# Replicape_B0.net
KiCad netlist of a schematic drawn in EAGLE
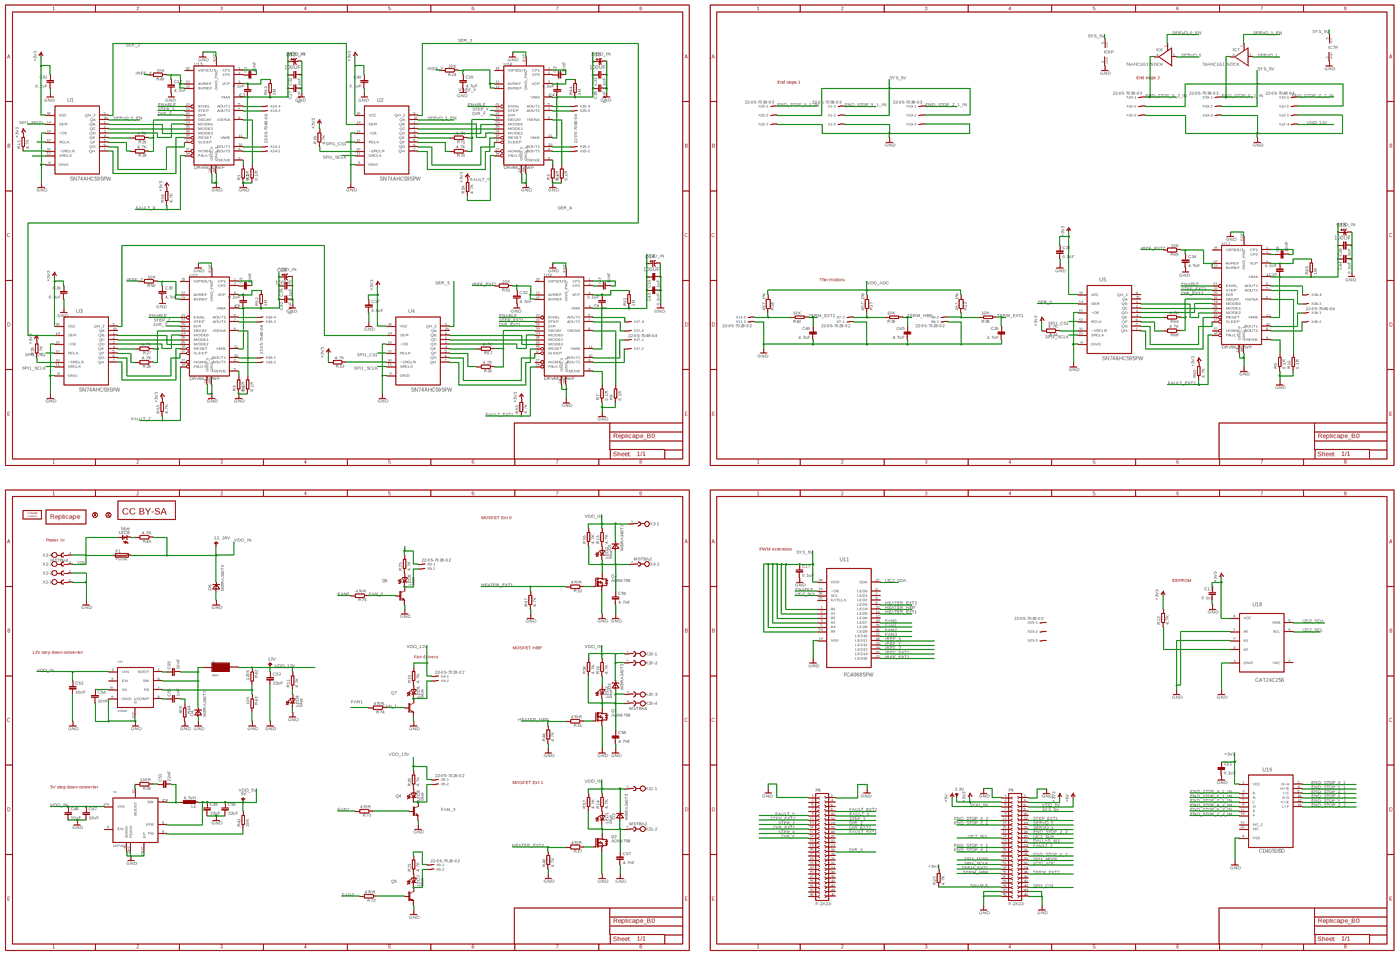
[diagram p0: schematic, sheet 1, overview]
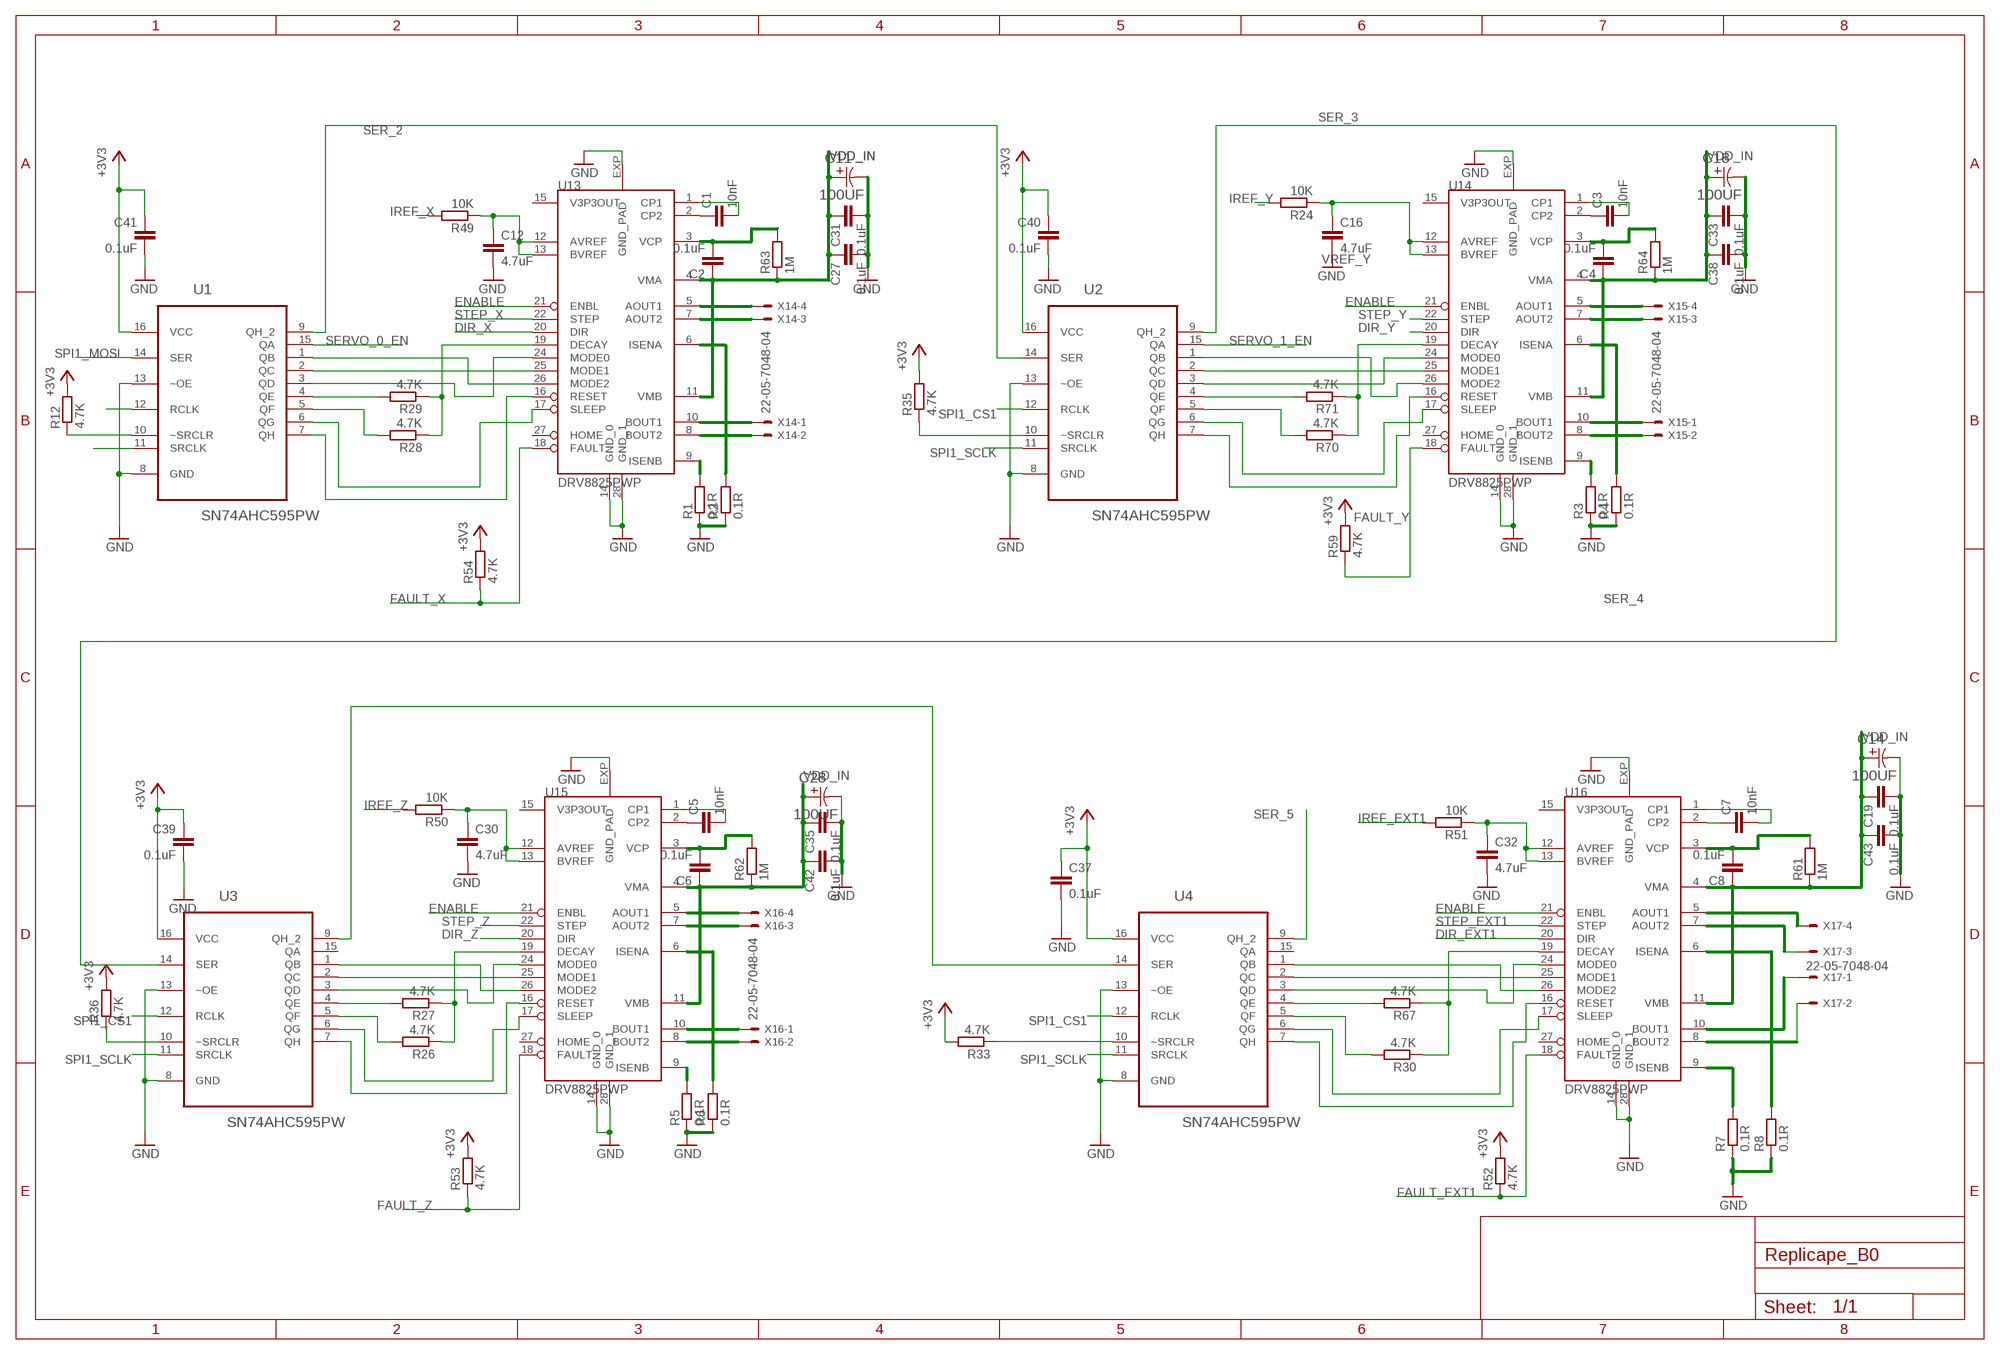
[diagram p1: schematic, sheet 1, part 1 of 4]
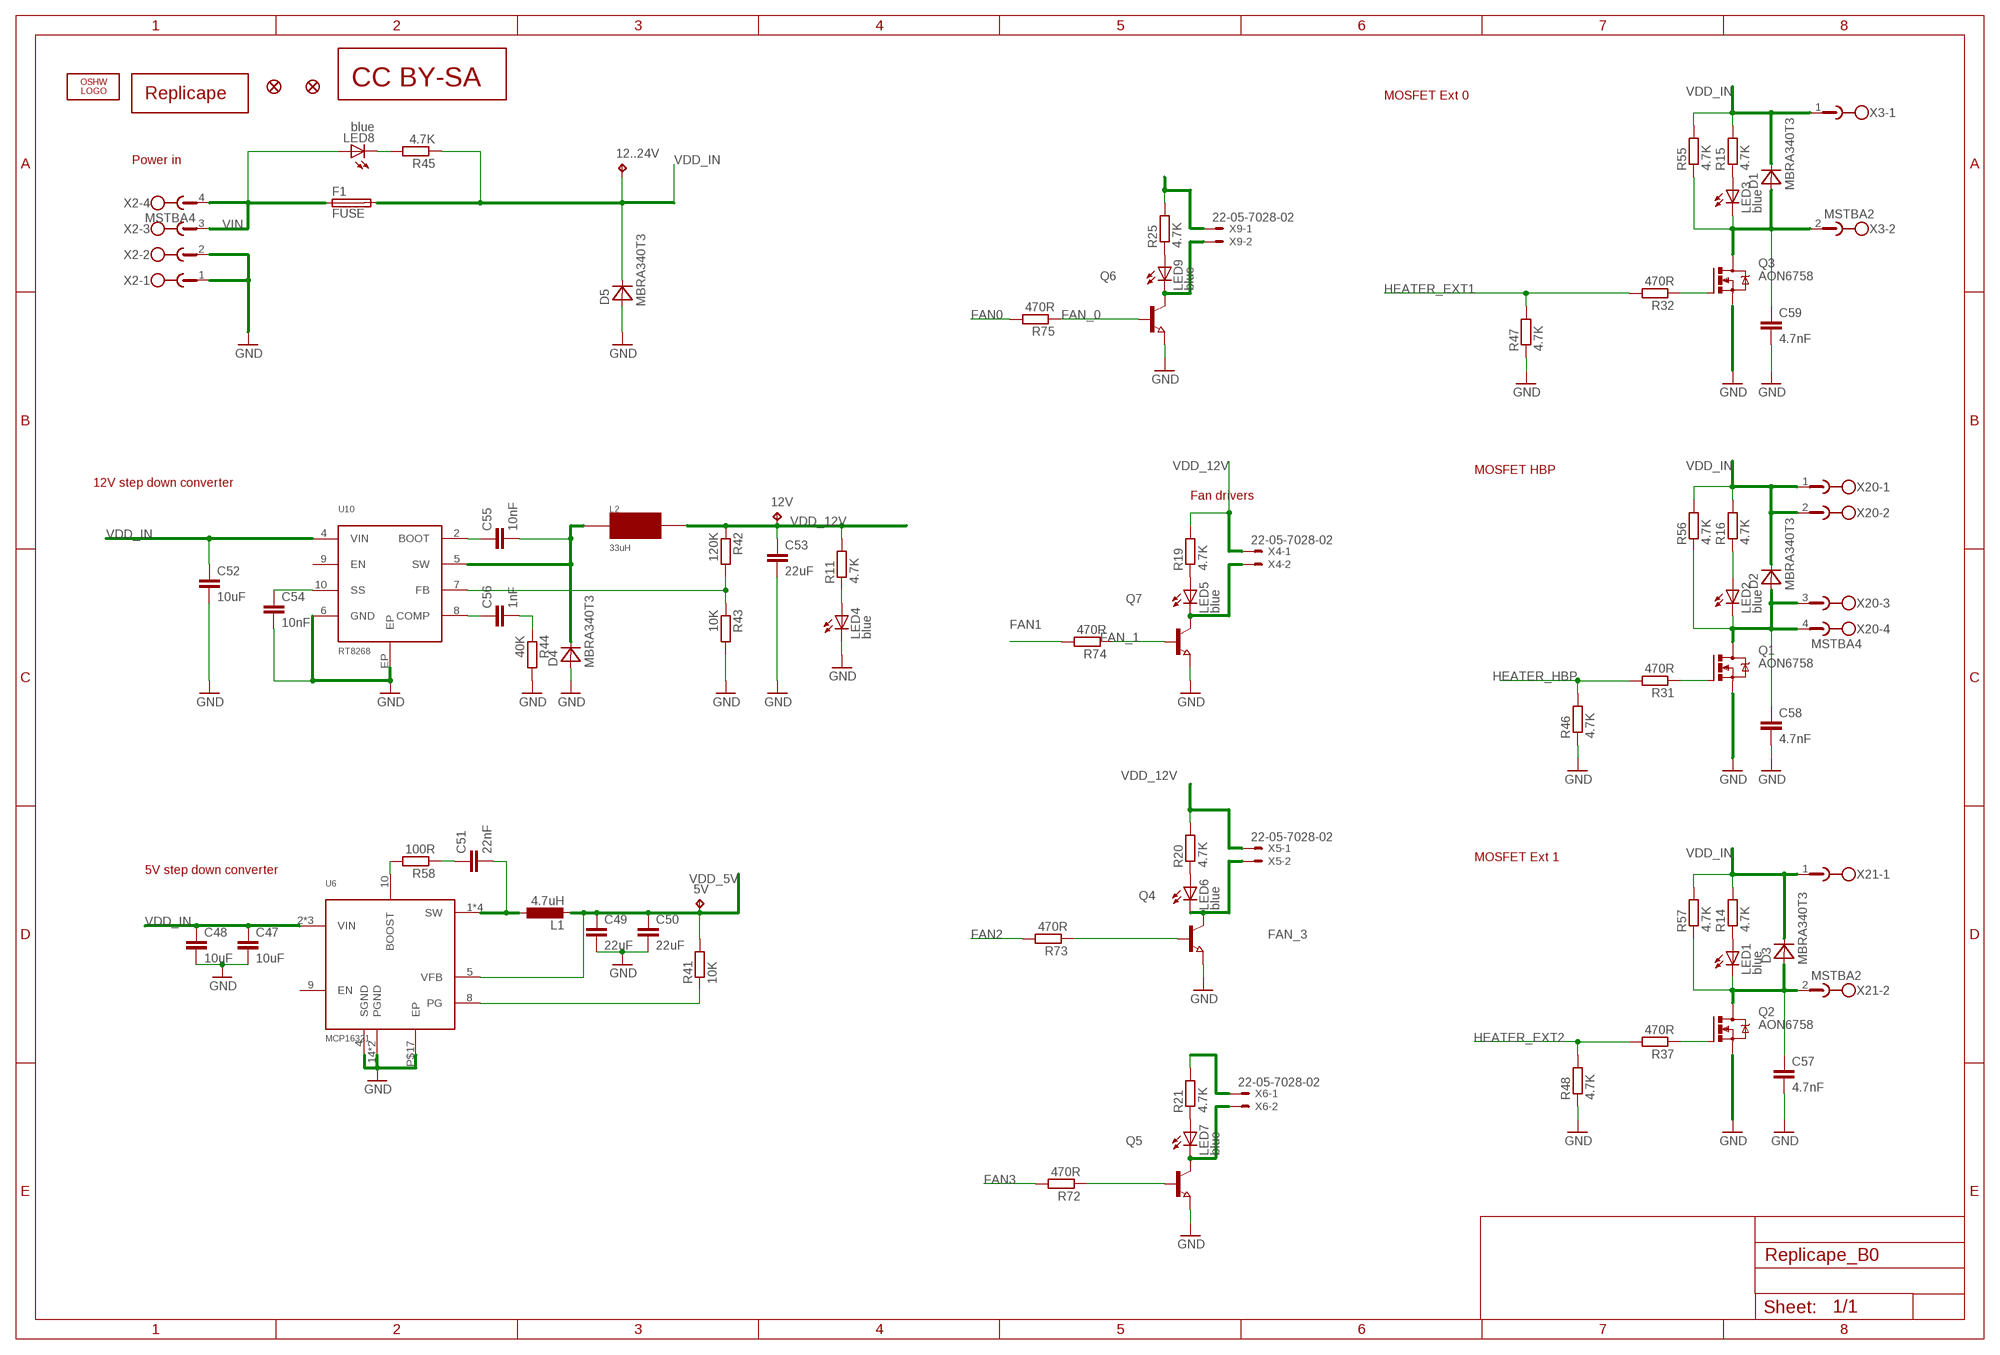
[diagram p2: schematic, sheet 1, part 2 of 4]
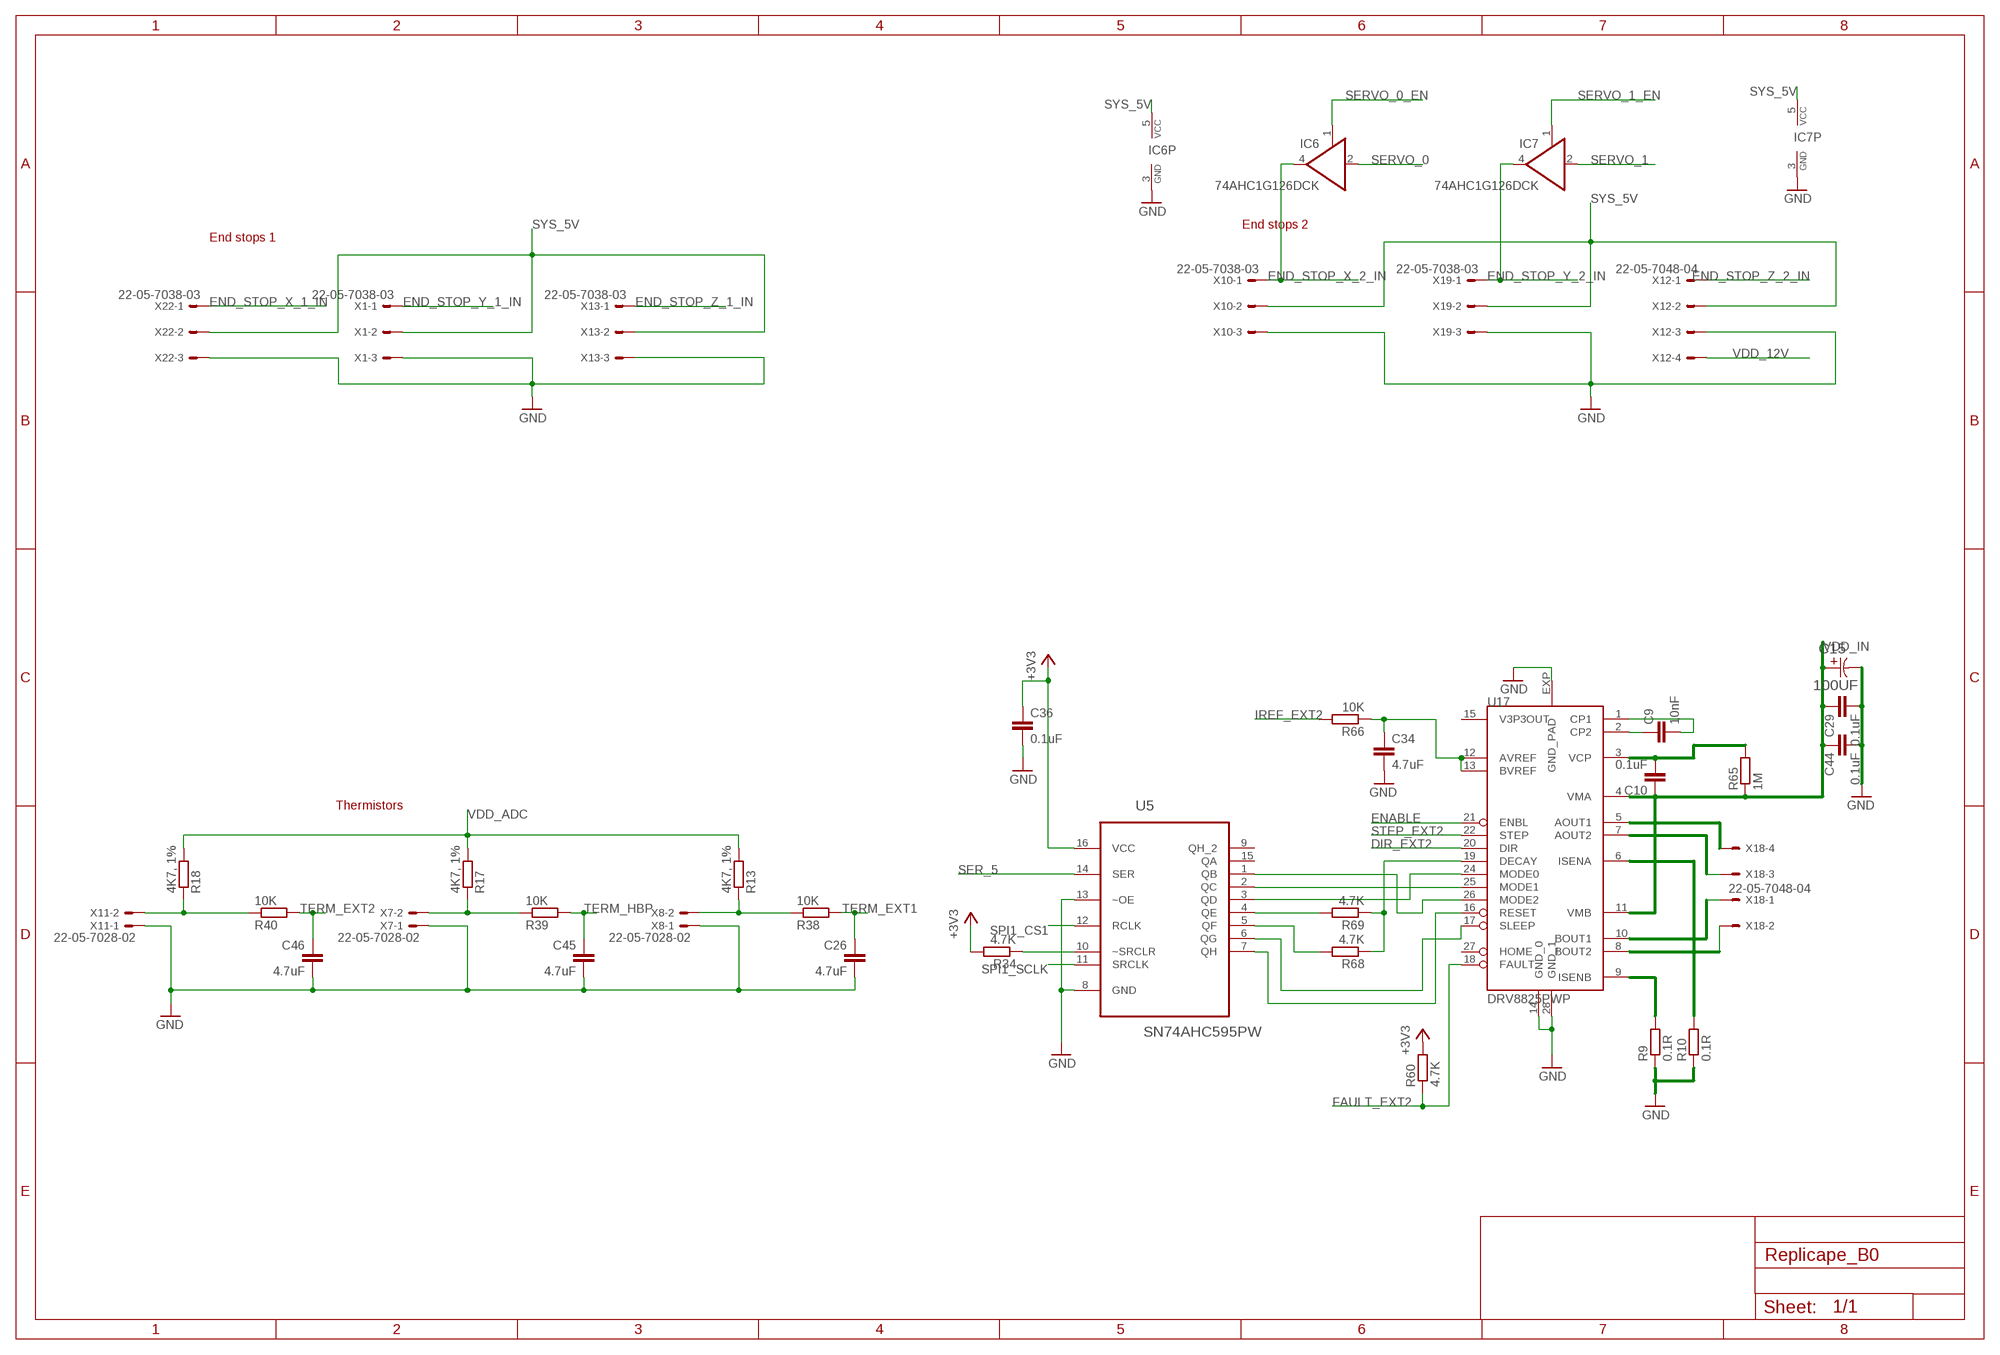
[diagram p3: schematic, sheet 1, part 3 of 4]
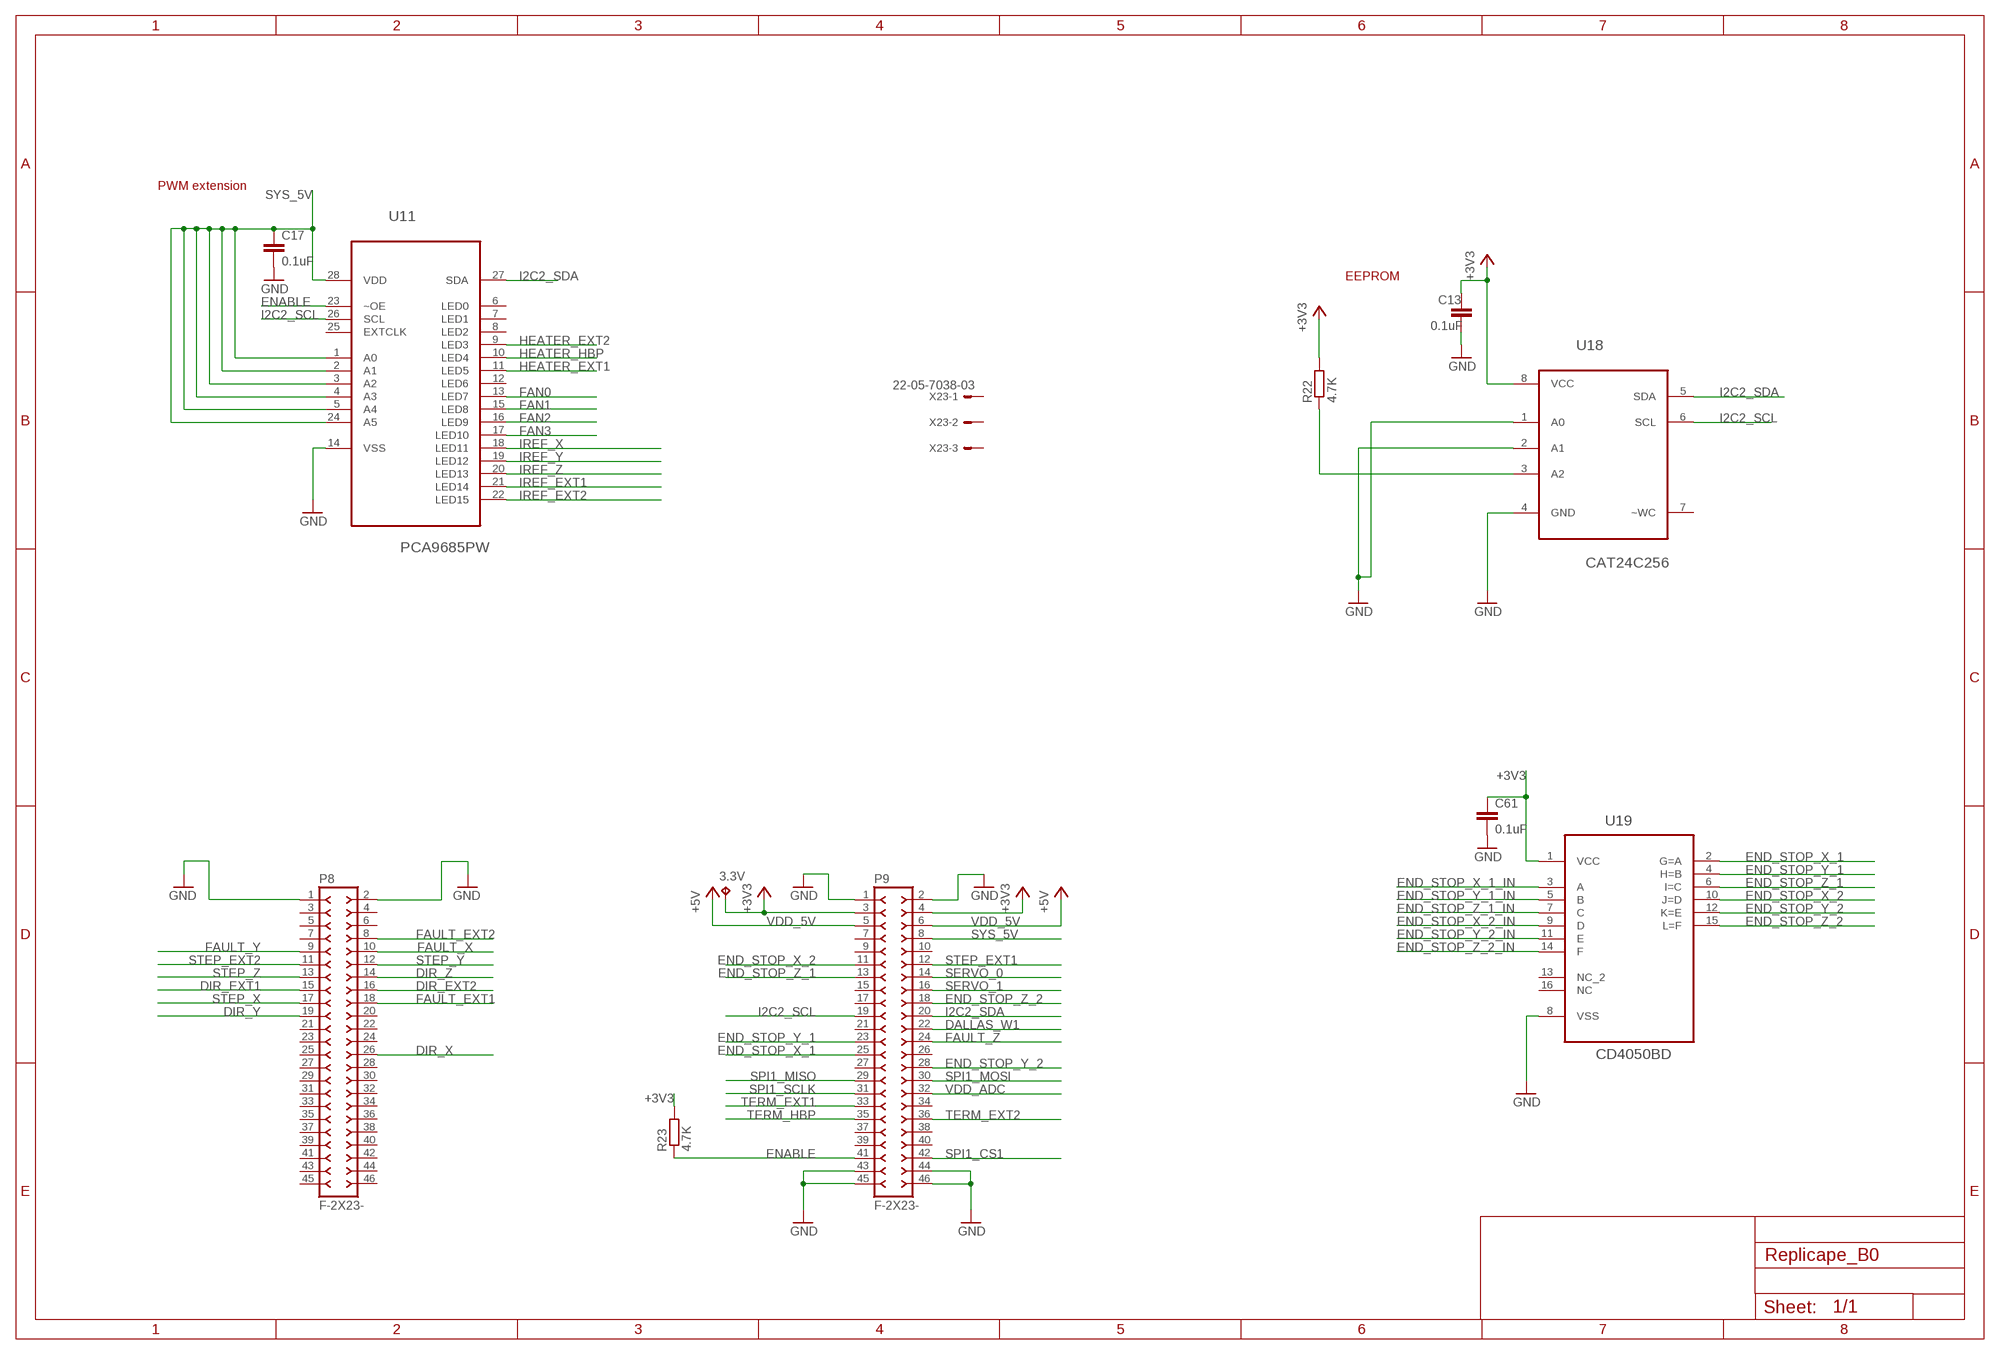
[diagram p4: schematic, sheet 1, part 4 of 4]

(export (version "E")
  (design (tool "Eeschema 10.0.6"))
  (components
    (comp (ref "3.3V")
      (value "TPB1,27")
      (footprint "eagle-import:B1,27")
      (libsource (lib "eagle-import") (part "TPB1,27"))
    )
    (comp (ref "5V")
      (value "TPB1,27")
      (footprint "eagle-import:B1,27")
      (libsource (lib "eagle-import") (part "TPB1,27"))
    )
    (comp (ref "12..24V")
      (value "TPB1,27")
      (footprint "eagle-import:B1,27")
      (libsource (lib "eagle-import") (part "TPB1,27"))
    )
    (comp (ref "12V")
      (value "TPB1,27")
      (footprint "eagle-import:B1,27")
      (libsource (lib "eagle-import") (part "TPB1,27"))
    )
    (comp (ref "C1")
      (value "10nF")
      (footprint "eagle-import:C0402")
      (libsource (lib "eagle-import") (part "C-EUC0402"))
    )
    (comp (ref "C2")
      (value "0.1uF")
      (footprint "eagle-import:C0402")
      (libsource (lib "eagle-import") (part "C-EUC0402"))
    )
    (comp (ref "C3")
      (value "10nF")
      (footprint "eagle-import:C0402")
      (libsource (lib "eagle-import") (part "C-EUC0402"))
    )
    (comp (ref "C4")
      (value "0.1uF")
      (footprint "eagle-import:C0402")
      (libsource (lib "eagle-import") (part "C-EUC0402"))
    )
    (comp (ref "C5")
      (value "10nF")
      (footprint "eagle-import:C0402")
      (libsource (lib "eagle-import") (part "C-EUC0402"))
    )
    (comp (ref "C6")
      (value "0.1uF")
      (footprint "eagle-import:C0402")
      (libsource (lib "eagle-import") (part "C-EUC0402"))
    )
    (comp (ref "C7")
      (value "10nF")
      (footprint "eagle-import:C0402")
      (libsource (lib "eagle-import") (part "C-EUC0402"))
    )
    (comp (ref "C8")
      (value "0.1uF")
      (footprint "eagle-import:C0402")
      (libsource (lib "eagle-import") (part "C-EUC0402"))
    )
    (comp (ref "C9")
      (value "10nF")
      (footprint "eagle-import:C0402")
      (libsource (lib "eagle-import") (part "C-EUC0402"))
    )
    (comp (ref "C10")
      (value "0.1uF")
      (footprint "eagle-import:C0402")
      (libsource (lib "eagle-import") (part "C-EUC0402"))
    )
    (comp (ref "C11")
      (value "100UF")
      (footprint "eagle-import:CAPAE660X800N")
      (fields (field (name "MPN") "EEE-FK1V101XP") (field (name "TOLERANCE") "±20 %"))
      (libsource (lib "eagle-import") (part "EEE--CASE-D8FK1V101XP"))
    )
    (comp (ref "C12")
      (value "4.7uF")
      (footprint "eagle-import:C0402")
      (libsource (lib "eagle-import") (part "C-EUC0402"))
    )
    (comp (ref "C13")
      (value "0.1uF")
      (footprint "eagle-import:C0402")
      (libsource (lib "eagle-import") (part "C-EUC0402"))
    )
    (comp (ref "C14")
      (value "100UF")
      (footprint "eagle-import:CAPAE660X800N")
      (fields (field (name "MPN") "EEE-FK1V101XP") (field (name "TOLERANCE") "±20 %"))
      (libsource (lib "eagle-import") (part "EEE--CASE-D8FK1V101XP"))
    )
    (comp (ref "C15")
      (value "100UF")
      (footprint "eagle-import:CAPAE660X800N")
      (fields (field (name "MPN") "EEE-FK1V101XP") (field (name "TOLERANCE") "±20 %"))
      (libsource (lib "eagle-import") (part "EEE--CASE-D8FK1V101XP"))
    )
    (comp (ref "C16")
      (value "4.7uF")
      (footprint "eagle-import:C0402")
      (libsource (lib "eagle-import") (part "C-EUC0402"))
    )
    (comp (ref "C17")
      (value "0.1uF")
      (footprint "eagle-import:C0402")
      (libsource (lib "eagle-import") (part "C-EUC0402"))
    )
    (comp (ref "C18")
      (value "100UF")
      (footprint "eagle-import:CAPAE660X800N")
      (fields (field (name "MPN") "EEE-FK1V101XP") (field (name "TOLERANCE") "±20 %"))
      (libsource (lib "eagle-import") (part "EEE--CASE-D8FK1V101XP"))
    )
    (comp (ref "C19")
      (value "0.1uF")
      (footprint "eagle-import:C0402")
      (libsource (lib "eagle-import") (part "C-EUC0402"))
    )
    (comp (ref "C26")
      (value "4.7uF")
      (footprint "eagle-import:C0402")
      (libsource (lib "eagle-import") (part "C-EUC0402"))
    )
    (comp (ref "C27")
      (value "0.1uF")
      (footprint "eagle-import:C0402")
      (libsource (lib "eagle-import") (part "C-EUC0402"))
    )
    (comp (ref "C28")
      (value "100UF")
      (footprint "eagle-import:CAPAE660X800N")
      (fields (field (name "MPN") "EEE-FK1V101XP") (field (name "TOLERANCE") "±20 %"))
      (libsource (lib "eagle-import") (part "EEE--CASE-D8FK1V101XP"))
    )
    (comp (ref "C29")
      (value "0.1uF")
      (footprint "eagle-import:C0402")
      (libsource (lib "eagle-import") (part "C-EUC0402"))
    )
    (comp (ref "C30")
      (value "4.7uF")
      (footprint "eagle-import:C0402")
      (libsource (lib "eagle-import") (part "C-EUC0402"))
    )
    (comp (ref "C31")
      (value "0.1uF")
      (footprint "eagle-import:C0402")
      (libsource (lib "eagle-import") (part "C-EUC0402"))
    )
    (comp (ref "C32")
      (value "4.7uF")
      (footprint "eagle-import:C0402")
      (libsource (lib "eagle-import") (part "C-EUC0402"))
    )
    (comp (ref "C33")
      (value "0.1uF")
      (footprint "eagle-import:C0402")
      (libsource (lib "eagle-import") (part "C-EUC0402"))
    )
    (comp (ref "C34")
      (value "4.7uF")
      (footprint "eagle-import:C0402")
      (libsource (lib "eagle-import") (part "C-EUC0402"))
    )
    (comp (ref "C35")
      (value "0.1uF")
      (footprint "eagle-import:C0402")
      (libsource (lib "eagle-import") (part "C-EUC0402"))
    )
    (comp (ref "C36")
      (value "0.1uF")
      (footprint "eagle-import:C0402")
      (libsource (lib "eagle-import") (part "C-EUC0402"))
    )
    (comp (ref "C37")
      (value "0.1uF")
      (footprint "eagle-import:C0402")
      (libsource (lib "eagle-import") (part "C-EUC0402"))
    )
    (comp (ref "C38")
      (value "0.1uF")
      (footprint "eagle-import:C0402")
      (libsource (lib "eagle-import") (part "C-EUC0402"))
    )
    (comp (ref "C39")
      (value "0.1uF")
      (footprint "eagle-import:C0402")
      (libsource (lib "eagle-import") (part "C-EUC0402"))
    )
    (comp (ref "C40")
      (value "0.1uF")
      (footprint "eagle-import:C0402")
      (libsource (lib "eagle-import") (part "C-EUC0402"))
    )
    (comp (ref "C41")
      (value "0.1uF")
      (footprint "eagle-import:C0402")
      (libsource (lib "eagle-import") (part "C-EUC0402"))
    )
    (comp (ref "C42")
      (value "0.1uF")
      (footprint "eagle-import:C0402")
      (libsource (lib "eagle-import") (part "C-EUC0402"))
    )
    (comp (ref "C43")
      (value "0.1uF")
      (footprint "eagle-import:C0402")
      (libsource (lib "eagle-import") (part "C-EUC0402"))
    )
    (comp (ref "C44")
      (value "0.1uF")
      (footprint "eagle-import:C0402")
      (libsource (lib "eagle-import") (part "C-EUC0402"))
    )
    (comp (ref "C45")
      (value "4.7uF")
      (footprint "eagle-import:C0402")
      (libsource (lib "eagle-import") (part "C-EUC0402"))
    )
    (comp (ref "C46")
      (value "4.7uF")
      (footprint "eagle-import:C0402")
      (libsource (lib "eagle-import") (part "C-EUC0402"))
    )
    (comp (ref "C47")
      (value "10uF")
      (footprint "eagle-import:C1206")
      (libsource (lib "eagle-import") (part "C-EUC1206"))
    )
    (comp (ref "C48")
      (value "10uF")
      (footprint "eagle-import:C1206")
      (libsource (lib "eagle-import") (part "C-EUC1206"))
    )
    (comp (ref "C49")
      (value "22uF")
      (footprint "eagle-import:C0805")
      (libsource (lib "eagle-import") (part "C-EUC0805"))
    )
    (comp (ref "C50")
      (value "22uF")
      (footprint "eagle-import:C0805")
      (libsource (lib "eagle-import") (part "C-EUC0805"))
    )
    (comp (ref "C51")
      (value "22nF")
      (footprint "eagle-import:C0402")
      (libsource (lib "eagle-import") (part "C-EUC0402"))
    )
    (comp (ref "C52")
      (value "10uF")
      (footprint "eagle-import:C1206")
      (libsource (lib "eagle-import") (part "C-EUC1206"))
    )
    (comp (ref "C53")
      (value "22uF")
      (footprint "eagle-import:C0805")
      (libsource (lib "eagle-import") (part "C-EUC0805"))
    )
    (comp (ref "C54")
      (value "10nF")
      (footprint "eagle-import:C0402")
      (libsource (lib "eagle-import") (part "C-EUC0402"))
    )
    (comp (ref "C55")
      (value "10nF")
      (footprint "eagle-import:C0402")
      (libsource (lib "eagle-import") (part "C-EUC0402"))
    )
    (comp (ref "C56")
      (value "1nF")
      (footprint "eagle-import:C0402")
      (libsource (lib "eagle-import") (part "C-EUC0402"))
    )
    (comp (ref "C57")
      (value "4.7nF")
      (footprint "eagle-import:C0402")
      (libsource (lib "eagle-import") (part "C-EUC0402"))
    )
    (comp (ref "C58")
      (value "4.7nF")
      (footprint "eagle-import:C0402")
      (libsource (lib "eagle-import") (part "C-EUC0402"))
    )
    (comp (ref "C59")
      (value "4.7nF")
      (footprint "eagle-import:C0402")
      (libsource (lib "eagle-import") (part "C-EUC0402"))
    )
    (comp (ref "C61")
      (value "0.1uF")
      (footprint "eagle-import:C0402")
      (libsource (lib "eagle-import") (part "C-EUC0402"))
    )
    (comp (ref "D1")
      (value "MBRA340T3")
      (footprint "eagle-import:SMA")
      (libsource (lib "eagle-import") (part "MBRA340T3"))
    )
    (comp (ref "D2")
      (value "MBRA340T3")
      (footprint "eagle-import:SMA")
      (libsource (lib "eagle-import") (part "MBRA340T3"))
    )
    (comp (ref "D3")
      (value "MBRA340T3")
      (footprint "eagle-import:SMA")
      (libsource (lib "eagle-import") (part "MBRA340T3"))
    )
    (comp (ref "D4")
      (value "MBRA340T3")
      (footprint "eagle-import:SMA")
      (libsource (lib "eagle-import") (part "MBRA340T3"))
    )
    (comp (ref "D5")
      (value "MBRA340T3")
      (footprint "eagle-import:SMA")
      (libsource (lib "eagle-import") (part "MBRA340T3"))
    )
    (comp (ref "F1")
      (value "FUSE")
      (footprint "eagle-import:3557")
      (libsource (lib "eagle-import") (part "FUSE"))
    )
    (comp (ref "IC6")
      (value "74AHC1G126DCK")
      (footprint "eagle-import:SC70-5")
      (libsource (lib "eagle-import") (part "741G126DCKAHC"))
    )
    (comp (ref "IC7")
      (value "74AHC1G126DCK")
      (footprint "eagle-import:SC70-5")
      (libsource (lib "eagle-import") (part "741G126DCKAHC"))
    )
    (comp (ref "JP1")
      (value "FIDUCIAL1X2.5")
      (footprint "eagle-import:FIDUCIAL-1X2.5")
      (libsource (lib "eagle-import") (part "FIDUCIAL1X2.5"))
    )
    (comp (ref "JP2")
      (value "FIDUCIAL1X2.5")
      (footprint "eagle-import:FIDUCIAL-1X2.5")
      (libsource (lib "eagle-import") (part "FIDUCIAL1X2.5"))
    )
    (comp (ref "L1")
      (value "4.7uH")
      (footprint "eagle-import:VLC5020")
      (libsource (lib "eagle-import") (part "L-EU"))
    )
    (comp (ref "L2")
      (value "33uH")
      (footprint "eagle-import:NR8040T330")
      (libsource (lib "eagle-import") (part "RT8040T330"))
    )
    (comp (ref "LED1")
      (value "blue")
      (footprint "eagle-import:CHIP-LED0603")
      (libsource (lib "eagle-import") (part "LEDCHIP-LED0603"))
    )
    (comp (ref "LED2")
      (value "blue")
      (footprint "eagle-import:CHIP-LED0603")
      (libsource (lib "eagle-import") (part "LEDCHIP-LED0603"))
    )
    (comp (ref "LED3")
      (value "blue")
      (footprint "eagle-import:CHIP-LED0603")
      (libsource (lib "eagle-import") (part "LEDCHIP-LED0603"))
    )
    (comp (ref "LED4")
      (value "blue")
      (footprint "eagle-import:CHIP-LED0603")
      (libsource (lib "eagle-import") (part "LEDCHIP-LED0603"))
    )
    (comp (ref "LED5")
      (value "blue")
      (footprint "eagle-import:CHIP-LED0603")
      (libsource (lib "eagle-import") (part "LEDCHIP-LED0603"))
    )
    (comp (ref "LED6")
      (value "blue")
      (footprint "eagle-import:CHIP-LED0603")
      (libsource (lib "eagle-import") (part "LEDCHIP-LED0603"))
    )
    (comp (ref "LED7")
      (value "blue")
      (footprint "eagle-import:CHIP-LED0603")
      (libsource (lib "eagle-import") (part "LEDCHIP-LED0603"))
    )
    (comp (ref "LED8")
      (value "blue")
      (footprint "eagle-import:CHIP-LED0603")
      (libsource (lib "eagle-import") (part "LEDCHIP-LED0603"))
    )
    (comp (ref "LED9")
      (value "blue")
      (footprint "eagle-import:CHIP-LED0603")
      (libsource (lib "eagle-import") (part "LEDCHIP-LED0603"))
    )
    (comp (ref "LOGO1")
      (value "OSHW_LOGO_FILLX0200-NT")
      (footprint "eagle-import:OSHW_FILLX200_NOTEXT")
      (libsource (lib "eagle-import") (part "OSHW_LOGO_FILLX0200-NT"))
    )
    (comp (ref "P8")
      (value "F-2X23-")
      (footprint "eagle-import:DIL-100-2X23")
      (libsource (lib "eagle-import") (part "F-2X23-"))
    )
    (comp (ref "P9")
      (value "F-2X23-")
      (footprint "eagle-import:DIL-100-2X23")
      (libsource (lib "eagle-import") (part "F-2X23-"))
    )
    (comp (ref "Q1")
      (value "AON6758")
      (footprint "eagle-import:8-DFN-EP-(5X6)")
      (libsource (lib "eagle-import") (part "AON6758"))
    )
    (comp (ref "Q2")
      (value "AON6758")
      (footprint "eagle-import:8-DFN-EP-(5X6)")
      (libsource (lib "eagle-import") (part "AON6758"))
    )
    (comp (ref "Q3")
      (value "AON6758")
      (footprint "eagle-import:8-DFN-EP-(5X6)")
      (libsource (lib "eagle-import") (part "AON6758"))
    )
    (comp (ref "Q4")
      (value "NPN-TRANSISTOR_SOT23")
      (footprint "eagle-import:SOT23")
      (libsource (lib "eagle-import") (part "NPN-TRANSISTOR_SOT23"))
    )
    (comp (ref "Q5")
      (value "NPN-TRANSISTOR_SOT23")
      (footprint "eagle-import:SOT23")
      (libsource (lib "eagle-import") (part "NPN-TRANSISTOR_SOT23"))
    )
    (comp (ref "Q6")
      (value "NPN-TRANSISTOR_SOT23")
      (footprint "eagle-import:SOT23")
      (libsource (lib "eagle-import") (part "NPN-TRANSISTOR_SOT23"))
    )
    (comp (ref "Q7")
      (value "NPN-TRANSISTOR_SOT23")
      (footprint "eagle-import:SOT23")
      (libsource (lib "eagle-import") (part "NPN-TRANSISTOR_SOT23"))
    )
    (comp (ref "R1")
      (value "0.1R")
      (footprint "eagle-import:R0805")
      (libsource (lib "eagle-import") (part "R-EU_R0805"))
    )
    (comp (ref "R2")
      (value "0.1R")
      (footprint "eagle-import:R0805")
      (libsource (lib "eagle-import") (part "R-EU_R0805"))
    )
    (comp (ref "R3")
      (value "0.1R")
      (footprint "eagle-import:R0805")
      (libsource (lib "eagle-import") (part "R-EU_R0805"))
    )
    (comp (ref "R4")
      (value "0.1R")
      (footprint "eagle-import:R0805")
      (libsource (lib "eagle-import") (part "R-EU_R0805"))
    )
    (comp (ref "R5")
      (value "0.1R")
      (footprint "eagle-import:R0805")
      (libsource (lib "eagle-import") (part "R-EU_R0805"))
    )
    (comp (ref "R6")
      (value "0.1R")
      (footprint "eagle-import:R0805")
      (libsource (lib "eagle-import") (part "R-EU_R0805"))
    )
    (comp (ref "R7")
      (value "0.1R")
      (footprint "eagle-import:R0805")
      (libsource (lib "eagle-import") (part "R-EU_R0805"))
    )
    (comp (ref "R8")
      (value "0.1R")
      (footprint "eagle-import:R0805")
      (libsource (lib "eagle-import") (part "R-EU_R0805"))
    )
    (comp (ref "R9")
      (value "0.1R")
      (footprint "eagle-import:R0805")
      (libsource (lib "eagle-import") (part "R-EU_R0805"))
    )
    (comp (ref "R10")
      (value "0.1R")
      (footprint "eagle-import:R0805")
      (libsource (lib "eagle-import") (part "R-EU_R0805"))
    )
    (comp (ref "R11")
      (value "4.7K")
      (footprint "eagle-import:R0402")
      (libsource (lib "eagle-import") (part "R-EU_R0402"))
    )
    (comp (ref "R12")
      (value "4.7K")
      (footprint "eagle-import:R0402")
      (libsource (lib "eagle-import") (part "R-EU_R0402"))
    )
    (comp (ref "R13")
      (value "4K7, 1%")
      (footprint "eagle-import:R0402")
      (libsource (lib "eagle-import") (part "R-EU_R0402"))
    )
    (comp (ref "R14")
      (value "4.7K")
      (footprint "eagle-import:R0402")
      (libsource (lib "eagle-import") (part "R-EU_R0402"))
    )
    (comp (ref "R15")
      (value "4.7K")
      (footprint "eagle-import:R0402")
      (libsource (lib "eagle-import") (part "R-EU_R0402"))
    )
    (comp (ref "R16")
      (value "4.7K")
      (footprint "eagle-import:R0402")
      (libsource (lib "eagle-import") (part "R-EU_R0402"))
    )
    (comp (ref "R17")
      (value "4K7, 1%")
      (footprint "eagle-import:R0402")
      (libsource (lib "eagle-import") (part "R-EU_R0402"))
    )
    (comp (ref "R18")
      (value "4K7, 1%")
      (footprint "eagle-import:R0402")
      (libsource (lib "eagle-import") (part "R-EU_R0402"))
    )
    (comp (ref "R19")
      (value "4.7K")
      (footprint "eagle-import:R0402")
      (libsource (lib "eagle-import") (part "R-EU_R0402"))
    )
    (comp (ref "R20")
      (value "4.7K")
      (footprint "eagle-import:R0402")
      (libsource (lib "eagle-import") (part "R-EU_R0402"))
    )
    (comp (ref "R21")
      (value "4.7K")
      (footprint "eagle-import:R0402")
      (libsource (lib "eagle-import") (part "R-EU_R0402"))
    )
    (comp (ref "R22")
      (value "4.7K")
      (footprint "eagle-import:R0402")
      (libsource (lib "eagle-import") (part "R-EU_R0402"))
    )
    (comp (ref "R23")
      (value "4.7K")
      (footprint "eagle-import:R0402")
      (libsource (lib "eagle-import") (part "R-EU_R0402"))
    )
    (comp (ref "R24")
      (value "10K")
      (footprint "eagle-import:R0402")
      (libsource (lib "eagle-import") (part "R-EU_R0402"))
    )
    (comp (ref "R25")
      (value "4.7K")
      (footprint "eagle-import:R0402")
      (libsource (lib "eagle-import") (part "R-EU_R0402"))
    )
    (comp (ref "R26")
      (value "4.7K")
      (footprint "eagle-import:R0402")
      (libsource (lib "eagle-import") (part "R-EU_R0402"))
    )
    (comp (ref "R27")
      (value "4.7K")
      (footprint "eagle-import:R0402")
      (libsource (lib "eagle-import") (part "R-EU_R0402"))
    )
    (comp (ref "R28")
      (value "4.7K")
      (footprint "eagle-import:R0402")
      (libsource (lib "eagle-import") (part "R-EU_R0402"))
    )
    (comp (ref "R29")
      (value "4.7K")
      (footprint "eagle-import:R0402")
      (libsource (lib "eagle-import") (part "R-EU_R0402"))
    )
    (comp (ref "R30")
      (value "4.7K")
      (footprint "eagle-import:R0402")
      (libsource (lib "eagle-import") (part "R-EU_R0402"))
    )
    (comp (ref "R31")
      (value "470R")
      (footprint "eagle-import:R0402")
      (libsource (lib "eagle-import") (part "R-EU_R0402"))
    )
    (comp (ref "R32")
      (value "470R")
      (footprint "eagle-import:R0402")
      (libsource (lib "eagle-import") (part "R-EU_R0402"))
    )
    (comp (ref "R33")
      (value "4.7K")
      (footprint "eagle-import:R0402")
      (libsource (lib "eagle-import") (part "R-EU_R0402"))
    )
    (comp (ref "R34")
      (value "4.7K")
      (footprint "eagle-import:R0402")
      (libsource (lib "eagle-import") (part "R-EU_R0402"))
    )
    (comp (ref "R35")
      (value "4.7K")
      (footprint "eagle-import:R0402")
      (libsource (lib "eagle-import") (part "R-EU_R0402"))
    )
    (comp (ref "R36")
      (value "4.7K")
      (footprint "eagle-import:R0402")
      (libsource (lib "eagle-import") (part "R-EU_R0402"))
    )
    (comp (ref "R37")
      (value "470R")
      (footprint "eagle-import:R0402")
      (libsource (lib "eagle-import") (part "R-EU_R0402"))
    )
    (comp (ref "R38")
      (value "10K")
      (footprint "eagle-import:R0402")
      (libsource (lib "eagle-import") (part "R-EU_R0402"))
    )
    (comp (ref "R39")
      (value "10K")
      (footprint "eagle-import:R0402")
      (libsource (lib "eagle-import") (part "R-EU_R0402"))
    )
    (comp (ref "R40")
      (value "10K")
      (footprint "eagle-import:R0402")
      (libsource (lib "eagle-import") (part "R-EU_R0402"))
    )
    (comp (ref "R41")
      (value "10K")
      (footprint "eagle-import:R0402")
      (libsource (lib "eagle-import") (part "R-EU_R0402"))
    )
    (comp (ref "R42")
      (value "120K")
      (footprint "eagle-import:R0402")
      (libsource (lib "eagle-import") (part "R-EU_R0402"))
    )
    (comp (ref "R43")
      (value "10K")
      (footprint "eagle-import:R0402")
      (libsource (lib "eagle-import") (part "R-EU_R0402"))
    )
    (comp (ref "R44")
      (value "40K")
      (footprint "eagle-import:R0402")
      (libsource (lib "eagle-import") (part "R-EU_R0402"))
    )
    (comp (ref "R45")
      (value "4.7K")
      (footprint "eagle-import:R0402")
      (libsource (lib "eagle-import") (part "R-EU_R0402"))
    )
    (comp (ref "R46")
      (value "4.7K")
      (footprint "eagle-import:R0402")
      (libsource (lib "eagle-import") (part "R-EU_R0402"))
    )
    (comp (ref "R47")
      (value "4.7K")
      (footprint "eagle-import:R0402")
      (libsource (lib "eagle-import") (part "R-EU_R0402"))
    )
    (comp (ref "R48")
      (value "4.7K")
      (footprint "eagle-import:R0402")
      (libsource (lib "eagle-import") (part "R-EU_R0402"))
    )
    (comp (ref "R49")
      (value "10K")
      (footprint "eagle-import:R0402")
      (libsource (lib "eagle-import") (part "R-EU_R0402"))
    )
    (comp (ref "R50")
      (value "10K")
      (footprint "eagle-import:R0402")
      (libsource (lib "eagle-import") (part "R-EU_R0402"))
    )
    (comp (ref "R51")
      (value "10K")
      (footprint "eagle-import:R0402")
      (libsource (lib "eagle-import") (part "R-EU_R0402"))
    )
    (comp (ref "R52")
      (value "4.7K")
      (footprint "eagle-import:R0402")
      (libsource (lib "eagle-import") (part "R-EU_R0402"))
    )
    (comp (ref "R53")
      (value "4.7K")
      (footprint "eagle-import:R0402")
      (libsource (lib "eagle-import") (part "R-EU_R0402"))
    )
    (comp (ref "R54")
      (value "4.7K")
      (footprint "eagle-import:R0402")
      (libsource (lib "eagle-import") (part "R-EU_R0402"))
    )
    (comp (ref "R55")
      (value "4.7K")
      (footprint "eagle-import:R0402")
      (libsource (lib "eagle-import") (part "R-EU_R0402"))
    )
    (comp (ref "R56")
      (value "4.7K")
      (footprint "eagle-import:R0402")
      (libsource (lib "eagle-import") (part "R-EU_R0402"))
    )
    (comp (ref "R57")
      (value "4.7K")
      (footprint "eagle-import:R0402")
      (libsource (lib "eagle-import") (part "R-EU_R0402"))
    )
    (comp (ref "R58")
      (value "100R")
      (footprint "eagle-import:R0402")
      (libsource (lib "eagle-import") (part "R-EU_R0402"))
    )
    (comp (ref "R59")
      (value "4.7K")
      (footprint "eagle-import:R0402")
      (libsource (lib "eagle-import") (part "R-EU_R0402"))
    )
    (comp (ref "R60")
      (value "4.7K")
      (footprint "eagle-import:R0402")
      (libsource (lib "eagle-import") (part "R-EU_R0402"))
    )
    (comp (ref "R61")
      (value "1M")
      (footprint "eagle-import:R0402")
      (libsource (lib "eagle-import") (part "R-EU_R0402"))
    )
    (comp (ref "R62")
      (value "1M")
      (footprint "eagle-import:R0402")
      (libsource (lib "eagle-import") (part "R-EU_R0402"))
    )
    (comp (ref "R63")
      (value "1M")
      (footprint "eagle-import:R0402")
      (libsource (lib "eagle-import") (part "R-EU_R0402"))
    )
    (comp (ref "R64")
      (value "1M")
      (footprint "eagle-import:R0402")
      (libsource (lib "eagle-import") (part "R-EU_R0402"))
    )
    (comp (ref "R65")
      (value "1M")
      (footprint "eagle-import:R0402")
      (libsource (lib "eagle-import") (part "R-EU_R0402"))
    )
    (comp (ref "R66")
      (value "10K")
      (footprint "eagle-import:R0402")
      (libsource (lib "eagle-import") (part "R-EU_R0402"))
    )
    (comp (ref "R67")
      (value "4.7K")
      (footprint "eagle-import:R0402")
      (libsource (lib "eagle-import") (part "R-EU_R0402"))
    )
    (comp (ref "R68")
      (value "4.7K")
      (footprint "eagle-import:R0402")
      (libsource (lib "eagle-import") (part "R-EU_R0402"))
    )
    (comp (ref "R69")
      (value "4.7K")
      (footprint "eagle-import:R0402")
      (libsource (lib "eagle-import") (part "R-EU_R0402"))
    )
    (comp (ref "R70")
      (value "4.7K")
      (footprint "eagle-import:R0402")
      (libsource (lib "eagle-import") (part "R-EU_R0402"))
    )
    (comp (ref "R71")
      (value "4.7K")
      (footprint "eagle-import:R0402")
      (libsource (lib "eagle-import") (part "R-EU_R0402"))
    )
    (comp (ref "R72")
      (value "470R")
      (footprint "eagle-import:R0402")
      (libsource (lib "eagle-import") (part "R-EU_R0402"))
    )
    (comp (ref "R73")
      (value "470R")
      (footprint "eagle-import:R0402")
      (libsource (lib "eagle-import") (part "R-EU_R0402"))
    )
    (comp (ref "R74")
      (value "470R")
      (footprint "eagle-import:R0402")
      (libsource (lib "eagle-import") (part "R-EU_R0402"))
    )
    (comp (ref "R75")
      (value "470R")
      (footprint "eagle-import:R0402")
      (libsource (lib "eagle-import") (part "R-EU_R0402"))
    )
    (comp (ref "U$2")
      (value "REPLICAPE-LOGO")
      (footprint "eagle-import:REPLICAPE-LOGO")
      (libsource (lib "eagle-import") (part "REPLICAPE-LOGO"))
    )
    (comp (ref "U$3")
      (value "CC-BY-SA")
      (footprint "eagle-import:CC-BY-SA")
      (libsource (lib "eagle-import") (part "CC-BY-SA"))
    )
    (comp (ref "U1")
      (value "SN74AHC595PW")
      (footprint "eagle-import:SOP65P640X120-16N")
      (libsource (lib "eagle-import") (part "SN74AHC595PW"))
    )
    (comp (ref "U2")
      (value "SN74AHC595PW")
      (footprint "eagle-import:SOP65P640X120-16N")
      (libsource (lib "eagle-import") (part "SN74AHC595PW"))
    )
    (comp (ref "U3")
      (value "SN74AHC595PW")
      (footprint "eagle-import:SOP65P640X120-16N")
      (libsource (lib "eagle-import") (part "SN74AHC595PW"))
    )
    (comp (ref "U4")
      (value "SN74AHC595PW")
      (footprint "eagle-import:SOP65P640X120-16N")
      (libsource (lib "eagle-import") (part "SN74AHC595PW"))
    )
    (comp (ref "U5")
      (value "SN74AHC595PW")
      (footprint "eagle-import:SOP65P640X120-16N")
      (libsource (lib "eagle-import") (part "SN74AHC595PW"))
    )
    (comp (ref "U6")
      (value "MCP16321")
      (footprint "eagle-import:QFN-16")
      (libsource (lib "eagle-import") (part "MCP16321"))
    )
    (comp (ref "U10")
      (value "RT8268")
      (footprint "eagle-import:MSOP10")
      (libsource (lib "eagle-import") (part "RT8268"))
    )
    (comp (ref "U11")
      (value "PCA9685PW")
      (footprint "eagle-import:SOP65P640X110-28N")
      (libsource (lib "eagle-import") (part "PCA9685PW"))
    )
    (comp (ref "U13")
      (value "DRV8825PWP")
      (footprint "eagle-import:TSSOP-28")
      (libsource (lib "eagle-import") (part "DRV8825PWP"))
    )
    (comp (ref "U14")
      (value "DRV8825PWP")
      (footprint "eagle-import:TSSOP-28")
      (libsource (lib "eagle-import") (part "DRV8825PWP"))
    )
    (comp (ref "U15")
      (value "DRV8825PWP")
      (footprint "eagle-import:TSSOP-28")
      (libsource (lib "eagle-import") (part "DRV8825PWP"))
    )
    (comp (ref "U16")
      (value "DRV8825PWP")
      (footprint "eagle-import:TSSOP-28")
      (libsource (lib "eagle-import") (part "DRV8825PWP"))
    )
    (comp (ref "U17")
      (value "DRV8825PWP")
      (footprint "eagle-import:TSSOP-28")
      (libsource (lib "eagle-import") (part "DRV8825PWP"))
    )
    (comp (ref "U18")
      (value "CAT24C256")
      (footprint "eagle-import:SOIC127P600X175-8N")
      (libsource (lib "eagle-import") (part "CAT24C256"))
    )
    (comp (ref "U19")
      (value "CD4050BD")
      (footprint "eagle-import:SOIC127P600X175-16N")
      (libsource (lib "eagle-import") (part "CD4050BD"))
    )
    (comp (ref "X1")
      (value "22-05-7038-03")
      (footprint "eagle-import:7395-03")
      (libsource (lib "eagle-import") (part "22-?-0305-7038"))
    )
    (comp (ref "X2")
      (value "MSTBA4")
      (footprint "eagle-import:MSTBA4")
      (fields (field (name "MF") "FARNELL") (field (name "MPN") "1757268"))
      (libsource (lib "eagle-import") (part "MSTBA4"))
    )
    (comp (ref "X3")
      (value "MSTBA2")
      (footprint "eagle-import:MSTBA2")
      (fields (field (name "MF") "FARNELL") (field (name "MPN") "1757242"))
      (libsource (lib "eagle-import") (part "MSTBA2"))
    )
    (comp (ref "X4")
      (value "22-05-7028-02")
      (footprint "eagle-import:7395-02")
      (libsource (lib "eagle-import") (part "22-?-0205-7028"))
    )
    (comp (ref "X5")
      (value "22-05-7028-02")
      (footprint "eagle-import:7395-02")
      (libsource (lib "eagle-import") (part "22-?-0205-7028"))
    )
    (comp (ref "X6")
      (value "22-05-7028-02")
      (footprint "eagle-import:7395-02")
      (libsource (lib "eagle-import") (part "22-?-0205-7028"))
    )
    (comp (ref "X7")
      (value "22-05-7028-02")
      (footprint "eagle-import:7395-02")
      (libsource (lib "eagle-import") (part "22-?-0205-7028"))
    )
    (comp (ref "X8")
      (value "22-05-7028-02")
      (footprint "eagle-import:7395-02")
      (libsource (lib "eagle-import") (part "22-?-0205-7028"))
    )
    (comp (ref "X9")
      (value "22-05-7028-02")
      (footprint "eagle-import:7395-02")
      (libsource (lib "eagle-import") (part "22-?-0205-7028"))
    )
    (comp (ref "X10")
      (value "22-05-7038-03")
      (footprint "eagle-import:7395-03")
      (libsource (lib "eagle-import") (part "22-?-0305-7038"))
    )
    (comp (ref "X11")
      (value "22-05-7028-02")
      (footprint "eagle-import:7395-02")
      (libsource (lib "eagle-import") (part "22-?-0205-7028"))
    )
    (comp (ref "X12")
      (value "22-05-7048-04")
      (footprint "eagle-import:7395-04")
      (libsource (lib "eagle-import") (part "22-?-0405-7048"))
    )
    (comp (ref "X13")
      (value "22-05-7038-03")
      (footprint "eagle-import:7395-03")
      (libsource (lib "eagle-import") (part "22-?-0305-7038"))
    )
    (comp (ref "X14")
      (value "22-05-7048-04")
      (footprint "eagle-import:7395-04")
      (libsource (lib "eagle-import") (part "22-?-0405-7048"))
    )
    (comp (ref "X15")
      (value "22-05-7048-04")
      (footprint "eagle-import:7395-04")
      (libsource (lib "eagle-import") (part "22-?-0405-7048"))
    )
    (comp (ref "X16")
      (value "22-05-7048-04")
      (footprint "eagle-import:7395-04")
      (libsource (lib "eagle-import") (part "22-?-0405-7048"))
    )
    (comp (ref "X17")
      (value "22-05-7048-04")
      (footprint "eagle-import:7395-04")
      (libsource (lib "eagle-import") (part "22-?-0405-7048"))
    )
    (comp (ref "X18")
      (value "22-05-7048-04")
      (footprint "eagle-import:7395-04")
      (libsource (lib "eagle-import") (part "22-?-0405-7048"))
    )
    (comp (ref "X19")
      (value "22-05-7038-03")
      (footprint "eagle-import:7395-03")
      (libsource (lib "eagle-import") (part "22-?-0305-7038"))
    )
    (comp (ref "X20")
      (value "MSTBA4")
      (footprint "eagle-import:MSTBA4")
      (fields (field (name "MF") "FARNELL") (field (name "MPN") "1757268"))
      (libsource (lib "eagle-import") (part "MSTBA4"))
    )
    (comp (ref "X21")
      (value "MSTBA2")
      (footprint "eagle-import:MSTBA2")
      (fields (field (name "MF") "FARNELL") (field (name "MPN") "1757242"))
      (libsource (lib "eagle-import") (part "MSTBA2"))
    )
    (comp (ref "X22")
      (value "22-05-7038-03")
      (footprint "eagle-import:7395-03")
      (libsource (lib "eagle-import") (part "22-?-0305-7038"))
    )
    (comp (ref "X23")
      (value "22-05-7038-03")
      (footprint "eagle-import:7395-03")
      (libsource (lib "eagle-import") (part "22-?-0305-7038"))
    )
  )
  (nets
    (net (code "1") (name "+3V3") (class "Default")
      (node (ref "3.3V") (pin "TP") (pinfunction "TP_TP") (pintype "input"))
      (node (ref "C13") (pin "1") (pinfunction "1_1") (pintype "passive"))
      (node (ref "C36") (pin "1") (pinfunction "1_1") (pintype "passive"))
      (node (ref "C37") (pin "1") (pinfunction "1_1") (pintype "passive"))
      (node (ref "C39") (pin "1") (pinfunction "1_1") (pintype "passive"))
      (node (ref "C40") (pin "1") (pinfunction "1_1") (pintype "passive"))
      (node (ref "C41") (pin "1") (pinfunction "1_1") (pintype "passive"))
      (node (ref "C61") (pin "1") (pinfunction "1_1") (pintype "passive"))
      (node (ref "P9") (pin "3") (pinfunction "3_3") (pintype "passive"))
      (node (ref "P9") (pin "4") (pinfunction "4_4") (pintype "passive"))
      (node (ref "R12") (pin "2") (pinfunction "2_2") (pintype "passive"))
      (node (ref "R22") (pin "2") (pinfunction "2_2") (pintype "passive"))
      (node (ref "R23") (pin "2") (pinfunction "2_2") (pintype "passive"))
      (node (ref "R33") (pin "2") (pinfunction "2_2") (pintype "passive"))
      (node (ref "R34") (pin "2") (pinfunction "2_2") (pintype "passive"))
      (node (ref "R35") (pin "2") (pinfunction "2_2") (pintype "passive"))
      (node (ref "R36") (pin "2") (pinfunction "2_2") (pintype "passive"))
      (node (ref "R52") (pin "2") (pinfunction "2_2") (pintype "passive"))
      (node (ref "R53") (pin "2") (pinfunction "2_2") (pintype "passive"))
      (node (ref "R54") (pin "2") (pinfunction "2_2") (pintype "passive"))
      (node (ref "R59") (pin "2") (pinfunction "2_2") (pintype "passive"))
      (node (ref "R60") (pin "2") (pinfunction "2_2") (pintype "passive"))
      (node (ref "U1") (pin "16") (pinfunction "VCC_16") (pintype "power_in"))
      (node (ref "U18") (pin "8") (pinfunction "VCC_8") (pintype "power_in"))
      (node (ref "U19") (pin "1") (pinfunction "VCC_1") (pintype "power_in"))
      (node (ref "U2") (pin "16") (pinfunction "VCC_16") (pintype "power_in"))
      (node (ref "U3") (pin "16") (pinfunction "VCC_16") (pintype "power_in"))
      (node (ref "U4") (pin "16") (pinfunction "VCC_16") (pintype "power_in"))
      (node (ref "U5") (pin "16") (pinfunction "VCC_16") (pintype "power_in"))
    )
    (net (code "2") (name "+5V") (class "Default")
      (node (ref "5V") (pin "TP") (pinfunction "TP_TP") (pintype "input"))
      (node (ref "C49") (pin "1") (pinfunction "1_1") (pintype "passive"))
      (node (ref "C50") (pin "1") (pinfunction "1_1") (pintype "passive"))
      (node (ref "L1") (pin "P$2") (pinfunction "2_P$2") (pintype "passive"))
      (node (ref "P9") (pin "5") (pinfunction "5_5") (pintype "passive"))
      (node (ref "P9") (pin "6") (pinfunction "6_6") (pintype "passive"))
      (node (ref "R41") (pin "2") (pinfunction "2_2") (pintype "passive"))
      (node (ref "U6") (pin "5") (pinfunction "VFB_5") (pintype "input"))
    )
    (net (code "3") (name "/DALLAS_W1") (class "Default")
      (node (ref "P9") (pin "22") (pinfunction "22_22") (pintype "passive"))
    )
    (net (code "4") (name "/DIR_EXT1") (class "Default")
      (node (ref "P8") (pin "15") (pinfunction "15_15") (pintype "passive"))
      (node (ref "U16") (pin "20") (pinfunction "DIR_20") (pintype "input"))
    )
    (net (code "5") (name "/DIR_EXT2") (class "Default")
      (node (ref "P8") (pin "16") (pinfunction "16_16") (pintype "passive"))
      (node (ref "U17") (pin "20") (pinfunction "DIR_20") (pintype "input"))
    )
    (net (code "6") (name "/DIR_X") (class "Default")
      (node (ref "P8") (pin "26") (pinfunction "26_26") (pintype "passive"))
      (node (ref "U13") (pin "20") (pinfunction "DIR_20") (pintype "input"))
    )
    (net (code "7") (name "/DIR_Y") (class "Default")
      (node (ref "P8") (pin "19") (pinfunction "19_19") (pintype "passive"))
      (node (ref "U14") (pin "20") (pinfunction "DIR_20") (pintype "input"))
    )
    (net (code "8") (name "/DIR_Z") (class "Default")
      (node (ref "P8") (pin "14") (pinfunction "14_14") (pintype "passive"))
      (node (ref "U15") (pin "20") (pinfunction "DIR_20") (pintype "input"))
    )
    (net (code "9") (name "/ENABLE") (class "Default")
      (node (ref "P9") (pin "41") (pinfunction "41_41") (pintype "passive"))
      (node (ref "R23") (pin "1") (pinfunction "1_1") (pintype "passive"))
      (node (ref "U11") (pin "23") (pinfunction "~{OE}_23") (pintype "input"))
      (node (ref "U13") (pin "21") (pinfunction "ENBL_21") (pintype "input"))
      (node (ref "U14") (pin "21") (pinfunction "ENBL_21") (pintype "input"))
      (node (ref "U15") (pin "21") (pinfunction "ENBL_21") (pintype "input"))
      (node (ref "U16") (pin "21") (pinfunction "ENBL_21") (pintype "input"))
      (node (ref "U17") (pin "21") (pinfunction "ENBL_21") (pintype "input"))
    )
    (net (code "10") (name "/END_STOP_X_1") (class "Default")
      (node (ref "P9") (pin "25") (pinfunction "25_25") (pintype "passive"))
      (node (ref "U19") (pin "2") (pinfunction "G=A_2") (pintype "output"))
    )
    (net (code "11") (name "/END_STOP_X_1_IN") (class "Default")
      (node (ref "U19") (pin "3") (pinfunction "A_3") (pintype "input"))
      (node (ref "X22") (pin "1") (pinfunction "S_1") (pintype "passive"))
    )
    (net (code "12") (name "/END_STOP_X_2") (class "Default")
      (node (ref "P9") (pin "11") (pinfunction "11_11") (pintype "passive"))
      (node (ref "U19") (pin "10") (pinfunction "J=D_10") (pintype "output"))
    )
    (net (code "13") (name "/END_STOP_X_2_IN") (class "Default")
      (node (ref "IC6") (pin "4") (pinfunction "O_4") (pintype "output"))
      (node (ref "U19") (pin "9") (pinfunction "D_9") (pintype "input"))
      (node (ref "X10") (pin "1") (pinfunction "S_1") (pintype "passive"))
    )
    (net (code "14") (name "/END_STOP_Y_1") (class "Default")
      (node (ref "P9") (pin "23") (pinfunction "23_23") (pintype "passive"))
      (node (ref "U19") (pin "4") (pinfunction "H=B_4") (pintype "output"))
    )
    (net (code "15") (name "/END_STOP_Y_1_IN") (class "Default")
      (node (ref "U19") (pin "5") (pinfunction "B_5") (pintype "input"))
      (node (ref "X1") (pin "1") (pinfunction "S_1") (pintype "passive"))
    )
    (net (code "16") (name "/END_STOP_Y_2") (class "Default")
      (node (ref "P9") (pin "28") (pinfunction "28_28") (pintype "passive"))
      (node (ref "U19") (pin "12") (pinfunction "K=E_12") (pintype "output"))
    )
    (net (code "17") (name "/END_STOP_Y_2_IN") (class "Default")
      (node (ref "IC7") (pin "4") (pinfunction "O_4") (pintype "output"))
      (node (ref "U19") (pin "11") (pinfunction "E_11") (pintype "input"))
      (node (ref "X19") (pin "1") (pinfunction "S_1") (pintype "passive"))
    )
    (net (code "18") (name "/END_STOP_Z_1") (class "Default")
      (node (ref "P9") (pin "13") (pinfunction "13_13") (pintype "passive"))
      (node (ref "U19") (pin "6") (pinfunction "I=C_6") (pintype "output"))
    )
    (net (code "19") (name "/END_STOP_Z_1_IN") (class "Default")
      (node (ref "U19") (pin "7") (pinfunction "C_7") (pintype "input"))
      (node (ref "X13") (pin "1") (pinfunction "S_1") (pintype "passive"))
    )
    (net (code "20") (name "/END_STOP_Z_2") (class "Default")
      (node (ref "P9") (pin "18") (pinfunction "18_18") (pintype "passive"))
      (node (ref "U19") (pin "15") (pinfunction "L=F_15") (pintype "output"))
    )
    (net (code "21") (name "/END_STOP_Z_2_IN") (class "Default")
      (node (ref "U19") (pin "14") (pinfunction "F_14") (pintype "input"))
      (node (ref "X12") (pin "1") (pinfunction "S_1") (pintype "passive"))
    )
    (net (code "22") (name "/FAN0") (class "Default")
      (node (ref "R75") (pin "2") (pinfunction "2_2") (pintype "passive"))
      (node (ref "U11") (pin "13") (pinfunction "LED7_13") (pintype "output"))
    )
    (net (code "23") (name "/FAN1") (class "Default")
      (node (ref "R74") (pin "2") (pinfunction "2_2") (pintype "passive"))
      (node (ref "U11") (pin "15") (pinfunction "LED8_15") (pintype "output"))
    )
    (net (code "24") (name "/FAN2") (class "Default")
      (node (ref "R73") (pin "2") (pinfunction "2_2") (pintype "passive"))
      (node (ref "U11") (pin "16") (pinfunction "LED9_16") (pintype "output"))
    )
    (net (code "25") (name "/FAN3") (class "Default")
      (node (ref "R72") (pin "2") (pinfunction "2_2") (pintype "passive"))
      (node (ref "U11") (pin "17") (pinfunction "LED10_17") (pintype "output"))
    )
    (net (code "26") (name "/FAN_0") (class "Default")
      (node (ref "Q6") (pin "1") (pinfunction "B_1") (pintype "passive"))
      (node (ref "R75") (pin "1") (pinfunction "1_1") (pintype "passive"))
    )
    (net (code "27") (name "/FAN_1") (class "Default")
      (node (ref "Q7") (pin "1") (pinfunction "B_1") (pintype "passive"))
      (node (ref "R74") (pin "1") (pinfunction "1_1") (pintype "passive"))
    )
    (net (code "28") (name "/FAN_3") (class "Default")
      (node (ref "Q5") (pin "1") (pinfunction "B_1") (pintype "passive"))
      (node (ref "R72") (pin "1") (pinfunction "1_1") (pintype "passive"))
    )
    (net (code "29") (name "/FAULT_EXT1") (class "Default")
      (node (ref "P8") (pin "18") (pinfunction "18_18") (pintype "passive"))
      (node (ref "R52") (pin "1") (pinfunction "1_1") (pintype "passive"))
      (node (ref "U16") (pin "18") (pinfunction "FAULT_18") (pintype "output"))
    )
    (net (code "30") (name "/FAULT_EXT2") (class "Default")
      (node (ref "P8") (pin "8") (pinfunction "8_8") (pintype "passive"))
      (node (ref "R60") (pin "1") (pinfunction "1_1") (pintype "passive"))
      (node (ref "U17") (pin "18") (pinfunction "FAULT_18") (pintype "output"))
    )
    (net (code "31") (name "/FAULT_X") (class "Default")
      (node (ref "P8") (pin "10") (pinfunction "10_10") (pintype "passive"))
      (node (ref "R54") (pin "1") (pinfunction "1_1") (pintype "passive"))
      (node (ref "U13") (pin "18") (pinfunction "FAULT_18") (pintype "output"))
    )
    (net (code "32") (name "/FAULT_Y") (class "Default")
      (node (ref "P8") (pin "9") (pinfunction "9_9") (pintype "passive"))
      (node (ref "R59") (pin "1") (pinfunction "1_1") (pintype "passive"))
      (node (ref "U14") (pin "18") (pinfunction "FAULT_18") (pintype "output"))
    )
    (net (code "33") (name "/FAULT_Z") (class "Default")
      (node (ref "P9") (pin "24") (pinfunction "24_24") (pintype "passive"))
      (node (ref "R53") (pin "1") (pinfunction "1_1") (pintype "passive"))
      (node (ref "U15") (pin "18") (pinfunction "FAULT_18") (pintype "output"))
    )
    (net (code "34") (name "/HEATER_EXT1") (class "Default")
      (node (ref "R32") (pin "2") (pinfunction "2_2") (pintype "passive"))
      (node (ref "R47") (pin "2") (pinfunction "2_2") (pintype "passive"))
      (node (ref "U11") (pin "11") (pinfunction "LED5_11") (pintype "output"))
    )
    (net (code "35") (name "/HEATER_EXT2") (class "Default")
      (node (ref "R37") (pin "2") (pinfunction "2_2") (pintype "passive"))
      (node (ref "R48") (pin "2") (pinfunction "2_2") (pintype "passive"))
      (node (ref "U11") (pin "9") (pinfunction "LED3_9") (pintype "output"))
    )
    (net (code "36") (name "/HEATER_HBP") (class "Default")
      (node (ref "R31") (pin "2") (pinfunction "2_2") (pintype "passive"))
      (node (ref "R46") (pin "2") (pinfunction "2_2") (pintype "passive"))
      (node (ref "U11") (pin "10") (pinfunction "LED4_10") (pintype "output"))
    )
    (net (code "37") (name "/I2C2_SCL") (class "Default")
      (node (ref "P9") (pin "19") (pinfunction "19_19") (pintype "passive"))
      (node (ref "U11") (pin "26") (pinfunction "SCL_26") (pintype "input"))
      (node (ref "U18") (pin "6") (pinfunction "SCL_6") (pintype "input"))
    )
    (net (code "38") (name "/I2C2_SDA") (class "Default")
      (node (ref "P9") (pin "20") (pinfunction "20_20") (pintype "passive"))
      (node (ref "U11") (pin "27") (pinfunction "SDA_27") (pintype "bidirectional"))
      (node (ref "U18") (pin "5") (pinfunction "SDA_5") (pintype "bidirectional"))
    )
    (net (code "39") (name "/IREF_EXT1") (class "Default")
      (node (ref "R51") (pin "2") (pinfunction "2_2") (pintype "passive"))
      (node (ref "U11") (pin "21") (pinfunction "LED14_21") (pintype "output"))
    )
    (net (code "40") (name "/IREF_EXT2") (class "Default")
      (node (ref "R66") (pin "2") (pinfunction "2_2") (pintype "passive"))
      (node (ref "U11") (pin "22") (pinfunction "LED15_22") (pintype "output"))
    )
    (net (code "41") (name "/IREF_X") (class "Default")
      (node (ref "R49") (pin "2") (pinfunction "2_2") (pintype "passive"))
      (node (ref "U11") (pin "18") (pinfunction "LED11_18") (pintype "output"))
    )
    (net (code "42") (name "/IREF_Y") (class "Default")
      (node (ref "R24") (pin "2") (pinfunction "2_2") (pintype "passive"))
      (node (ref "U11") (pin "19") (pinfunction "LED12_19") (pintype "output"))
    )
    (net (code "43") (name "/IREF_Z") (class "Default")
      (node (ref "R50") (pin "2") (pinfunction "2_2") (pintype "passive"))
      (node (ref "U11") (pin "20") (pinfunction "LED13_20") (pintype "output"))
    )
    (net (code "44") (name "/SERVO_0") (class "Default")
      (node (ref "IC6") (pin "2") (pinfunction "I_2") (pintype "input"))
      (node (ref "P9") (pin "14") (pinfunction "14_14") (pintype "passive"))
    )
    (net (code "45") (name "/SERVO_0_EN") (class "Default")
      (node (ref "IC6") (pin "1") (pinfunction "OE_1") (pintype "input"))
      (node (ref "U1") (pin "15") (pinfunction "QA_15") (pintype "output"))
    )
    (net (code "46") (name "/SERVO_1") (class "Default")
      (node (ref "IC7") (pin "2") (pinfunction "I_2") (pintype "input"))
      (node (ref "P9") (pin "16") (pinfunction "16_16") (pintype "passive"))
    )
    (net (code "47") (name "/SERVO_1_EN") (class "Default")
      (node (ref "IC7") (pin "1") (pinfunction "OE_1") (pintype "input"))
      (node (ref "U2") (pin "15") (pinfunction "QA_15") (pintype "output"))
    )
    (net (code "48") (name "/SER_2") (class "Default")
      (node (ref "U1") (pin "9") (pinfunction "QH_2_9") (pintype "output"))
      (node (ref "U2") (pin "14") (pinfunction "SER_14") (pintype "input"))
    )
    (net (code "49") (name "/SER_3") (class "Default")
      (node (ref "U2") (pin "9") (pinfunction "QH_2_9") (pintype "output"))
      (node (ref "U3") (pin "14") (pinfunction "SER_14") (pintype "input"))
    )
    (net (code "50") (name "/SER_4") (class "Default")
      (node (ref "U3") (pin "9") (pinfunction "QH_2_9") (pintype "output"))
      (node (ref "U4") (pin "14") (pinfunction "SER_14") (pintype "input"))
    )
    (net (code "51") (name "/SER_5") (class "Default")
      (node (ref "U4") (pin "9") (pinfunction "QH_2_9") (pintype "output"))
      (node (ref "U5") (pin "14") (pinfunction "SER_14") (pintype "input"))
    )
    (net (code "52") (name "/SPI1_CS1") (class "Default")
      (node (ref "P9") (pin "42") (pinfunction "42_42") (pintype "passive"))
      (node (ref "U1") (pin "12") (pinfunction "RCLK_12") (pintype "input"))
      (node (ref "U2") (pin "12") (pinfunction "RCLK_12") (pintype "input"))
      (node (ref "U3") (pin "12") (pinfunction "RCLK_12") (pintype "input"))
      (node (ref "U4") (pin "12") (pinfunction "RCLK_12") (pintype "input"))
      (node (ref "U5") (pin "12") (pinfunction "RCLK_12") (pintype "input"))
    )
    (net (code "53") (name "/SPI1_MISO") (class "Default")
      (node (ref "P9") (pin "29") (pinfunction "29_29") (pintype "passive"))
    )
    (net (code "54") (name "/SPI1_MOSI") (class "Default")
      (node (ref "P9") (pin "30") (pinfunction "30_30") (pintype "passive"))
      (node (ref "U1") (pin "14") (pinfunction "SER_14") (pintype "input"))
    )
    (net (code "55") (name "/SPI1_SCLK") (class "Default")
      (node (ref "P9") (pin "31") (pinfunction "31_31") (pintype "passive"))
      (node (ref "U1") (pin "11") (pinfunction "SRCLK_11") (pintype "input"))
      (node (ref "U2") (pin "11") (pinfunction "SRCLK_11") (pintype "input"))
      (node (ref "U3") (pin "11") (pinfunction "SRCLK_11") (pintype "input"))
      (node (ref "U4") (pin "11") (pinfunction "SRCLK_11") (pintype "input"))
      (node (ref "U5") (pin "11") (pinfunction "SRCLK_11") (pintype "input"))
    )
    (net (code "56") (name "/STEP_EXT1") (class "Default")
      (node (ref "P9") (pin "12") (pinfunction "12_12") (pintype "passive"))
      (node (ref "U16") (pin "22") (pinfunction "STEP_22") (pintype "input"))
    )
    (net (code "57") (name "/STEP_EXT2") (class "Default")
      (node (ref "P8") (pin "11") (pinfunction "11_11") (pintype "passive"))
      (node (ref "U17") (pin "22") (pinfunction "STEP_22") (pintype "input"))
    )
    (net (code "58") (name "/STEP_X") (class "Default")
      (node (ref "P8") (pin "17") (pinfunction "17_17") (pintype "passive"))
      (node (ref "U13") (pin "22") (pinfunction "STEP_22") (pintype "input"))
    )
    (net (code "59") (name "/STEP_Y") (class "Default")
      (node (ref "P8") (pin "12") (pinfunction "12_12") (pintype "passive"))
      (node (ref "U14") (pin "22") (pinfunction "STEP_22") (pintype "input"))
    )
    (net (code "60") (name "/STEP_Z") (class "Default")
      (node (ref "P8") (pin "13") (pinfunction "13_13") (pintype "passive"))
      (node (ref "U15") (pin "22") (pinfunction "STEP_22") (pintype "input"))
    )
    (net (code "61") (name "/SYS_5V") (class "Default")
      (node (ref "C17") (pin "1") (pinfunction "1_1") (pintype "passive"))
      (node (ref "IC6") (pin "5") (pinfunction "VCC_5") (pintype "power_in"))
      (node (ref "IC7") (pin "5") (pinfunction "VCC_5") (pintype "power_in"))
      (node (ref "P9") (pin "8") (pinfunction "8_8") (pintype "passive"))
      (node (ref "U11") (pin "1") (pinfunction "A0_1") (pintype "input"))
      (node (ref "U11") (pin "2") (pinfunction "A1_2") (pintype "input"))
      (node (ref "U11") (pin "24") (pinfunction "A5_24") (pintype "input"))
      (node (ref "U11") (pin "28") (pinfunction "VDD_28") (pintype "power_in"))
      (node (ref "U11") (pin "3") (pinfunction "A2_3") (pintype "input"))
      (node (ref "U11") (pin "4") (pinfunction "A3_4") (pintype "input"))
      (node (ref "U11") (pin "5") (pinfunction "A4_5") (pintype "input"))
      (node (ref "X1") (pin "2") (pinfunction "S_2") (pintype "passive"))
      (node (ref "X10") (pin "2") (pinfunction "S_2") (pintype "passive"))
      (node (ref "X12") (pin "2") (pinfunction "S_2") (pintype "passive"))
      (node (ref "X13") (pin "2") (pinfunction "S_2") (pintype "passive"))
      (node (ref "X19") (pin "2") (pinfunction "S_2") (pintype "passive"))
      (node (ref "X22") (pin "2") (pinfunction "S_2") (pintype "passive"))
    )
    (net (code "62") (name "/TERM_EXT1") (class "Default")
      (node (ref "C26") (pin "1") (pinfunction "1_1") (pintype "passive"))
      (node (ref "P9") (pin "33") (pinfunction "33_33") (pintype "passive"))
      (node (ref "R38") (pin "2") (pinfunction "2_2") (pintype "passive"))
    )
    (net (code "63") (name "/TERM_EXT2") (class "Default")
      (node (ref "C46") (pin "1") (pinfunction "1_1") (pintype "passive"))
      (node (ref "P9") (pin "36") (pinfunction "36_36") (pintype "passive"))
      (node (ref "R40") (pin "2") (pinfunction "2_2") (pintype "passive"))
    )
    (net (code "64") (name "/TERM_HBP") (class "Default")
      (node (ref "C45") (pin "1") (pinfunction "1_1") (pintype "passive"))
      (node (ref "P9") (pin "35") (pinfunction "35_35") (pintype "passive"))
      (node (ref "R39") (pin "2") (pinfunction "2_2") (pintype "passive"))
    )
    (net (code "65") (name "/VDD_12V") (class "Default")
      (node (ref "12V") (pin "TP") (pinfunction "TP_TP") (pintype "input"))
      (node (ref "C53") (pin "1") (pinfunction "1_1") (pintype "passive"))
      (node (ref "L2") (pin "P$1") (pinfunction "P$1_P$1") (pintype "passive"))
      (node (ref "R11") (pin "2") (pinfunction "2_2") (pintype "passive"))
      (node (ref "R19") (pin "2") (pinfunction "2_2") (pintype "passive"))
      (node (ref "R20") (pin "2") (pinfunction "2_2") (pintype "passive"))
      (node (ref "R21") (pin "2") (pinfunction "2_2") (pintype "passive"))
      (node (ref "R25") (pin "2") (pinfunction "2_2") (pintype "passive"))
      (node (ref "R42") (pin "1") (pinfunction "1_1") (pintype "passive"))
      (node (ref "X12") (pin "4") (pinfunction "S_4") (pintype "passive"))
      (node (ref "X4") (pin "1") (pinfunction "S_1") (pintype "passive"))
      (node (ref "X5") (pin "1") (pinfunction "S_1") (pintype "passive"))
      (node (ref "X6") (pin "1") (pinfunction "S_1") (pintype "passive"))
      (node (ref "X9") (pin "1") (pinfunction "S_1") (pintype "passive"))
    )
    (net (code "66") (name "/VDD_ADC") (class "Default")
      (node (ref "P9") (pin "32") (pinfunction "32_32") (pintype "passive"))
      (node (ref "R13") (pin "2") (pinfunction "2_2") (pintype "passive"))
      (node (ref "R17") (pin "2") (pinfunction "2_2") (pintype "passive"))
      (node (ref "R18") (pin "2") (pinfunction "2_2") (pintype "passive"))
    )
    (net (code "67") (name "/VDD_IN") (class "Default")
      (node (ref "12..24V") (pin "TP") (pinfunction "TP_TP") (pintype "input"))
      (node (ref "C10") (pin "1") (pinfunction "1_1") (pintype "passive"))
      (node (ref "C11") (pin "1") (pinfunction "1_1") (pintype "passive"))
      (node (ref "C14") (pin "1") (pinfunction "1_1") (pintype "passive"))
      (node (ref "C15") (pin "1") (pinfunction "1_1") (pintype "passive"))
      (node (ref "C18") (pin "1") (pinfunction "1_1") (pintype "passive"))
      (node (ref "C19") (pin "1") (pinfunction "1_1") (pintype "passive"))
      (node (ref "C2") (pin "1") (pinfunction "1_1") (pintype "passive"))
      (node (ref "C27") (pin "1") (pinfunction "1_1") (pintype "passive"))
      (node (ref "C28") (pin "1") (pinfunction "1_1") (pintype "passive"))
      (node (ref "C29") (pin "1") (pinfunction "1_1") (pintype "passive"))
      (node (ref "C31") (pin "1") (pinfunction "1_1") (pintype "passive"))
      (node (ref "C33") (pin "1") (pinfunction "1_1") (pintype "passive"))
      (node (ref "C35") (pin "1") (pinfunction "1_1") (pintype "passive"))
      (node (ref "C38") (pin "1") (pinfunction "1_1") (pintype "passive"))
      (node (ref "C4") (pin "1") (pinfunction "1_1") (pintype "passive"))
      (node (ref "C42") (pin "1") (pinfunction "1_1") (pintype "passive"))
      (node (ref "C43") (pin "1") (pinfunction "1_1") (pintype "passive"))
      (node (ref "C44") (pin "1") (pinfunction "1_1") (pintype "passive"))
      (node (ref "C47") (pin "1") (pinfunction "1_1") (pintype "passive"))
      (node (ref "C48") (pin "1") (pinfunction "1_1") (pintype "passive"))
      (node (ref "C52") (pin "1") (pinfunction "1_1") (pintype "passive"))
      (node (ref "C6") (pin "1") (pinfunction "1_1") (pintype "passive"))
      (node (ref "C8") (pin "1") (pinfunction "1_1") (pintype "passive"))
      (node (ref "D1") (pin "C") (pinfunction "C_C") (pintype "passive"))
      (node (ref "D2") (pin "C") (pinfunction "C_C") (pintype "passive"))
      (node (ref "D3") (pin "C") (pinfunction "C_C") (pintype "passive"))
      (node (ref "D5") (pin "C") (pinfunction "C_C") (pintype "passive"))
      (node (ref "F1") (pin "P$3") (pinfunction "2_P$3") (pintype "passive"))
      (node (ref "F1") (pin "P$4") (pinfunction "2_P$4") (pintype "passive"))
      (node (ref "R14") (pin "2") (pinfunction "2_2") (pintype "passive"))
      (node (ref "R15") (pin "2") (pinfunction "2_2") (pintype "passive"))
      (node (ref "R16") (pin "2") (pinfunction "2_2") (pintype "passive"))
      (node (ref "R45") (pin "1") (pinfunction "1_1") (pintype "passive"))
      (node (ref "R55") (pin "2") (pinfunction "2_2") (pintype "passive"))
      (node (ref "R56") (pin "2") (pinfunction "2_2") (pintype "passive"))
      (node (ref "R57") (pin "2") (pinfunction "2_2") (pintype "passive"))
      (node (ref "R61") (pin "1") (pinfunction "1_1") (pintype "passive"))
      (node (ref "R62") (pin "1") (pinfunction "1_1") (pintype "passive"))
      (node (ref "R63") (pin "1") (pinfunction "1_1") (pintype "passive"))
      (node (ref "R64") (pin "1") (pinfunction "1_1") (pintype "passive"))
      (node (ref "R65") (pin "1") (pinfunction "1_1") (pintype "passive"))
      (node (ref "U10") (pin "4") (pinfunction "VIN_4") (pintype "power_in"))
      (node (ref "U13") (pin "11") (pinfunction "VMB_11") (pintype "power_in"))
      (node (ref "U13") (pin "4") (pinfunction "VMA_4") (pintype "power_in"))
      (node (ref "U14") (pin "11") (pinfunction "VMB_11") (pintype "power_in"))
      (node (ref "U14") (pin "4") (pinfunction "VMA_4") (pintype "power_in"))
      (node (ref "U15") (pin "11") (pinfunction "VMB_11") (pintype "power_in"))
      (node (ref "U15") (pin "4") (pinfunction "VMA_4") (pintype "power_in"))
      (node (ref "U16") (pin "11") (pinfunction "VMB_11") (pintype "power_in"))
      (node (ref "U16") (pin "4") (pinfunction "VMA_4") (pintype "power_in"))
      (node (ref "U17") (pin "11") (pinfunction "VMB_11") (pintype "power_in"))
      (node (ref "U17") (pin "4") (pinfunction "VMA_4") (pintype "power_in"))
      (node (ref "U6") (pin "11") (pinfunction "VIN_11") (pintype "power_in"))
      (node (ref "U6") (pin "2") (pinfunction "VIN_2") (pintype "power_in"))
      (node (ref "U6") (pin "3") (pinfunction "VIN_3") (pintype "power_in"))
      (node (ref "X20") (pin "1") (pinfunction "1_1") (pintype "passive"))
      (node (ref "X20") (pin "2") (pinfunction "1_2") (pintype "passive"))
      (node (ref "X21") (pin "1") (pinfunction "1_1") (pintype "passive"))
      (node (ref "X3") (pin "1") (pinfunction "1_1") (pintype "passive"))
    )
    (net (code "68") (name "/VIN") (class "Default")
      (node (ref "F1") (pin "P$1") (pinfunction "1_P$1") (pintype "passive"))
      (node (ref "F1") (pin "P$2") (pinfunction "1_P$2") (pintype "passive"))
      (node (ref "LED8") (pin "A") (pinfunction "A_A") (pintype "passive"))
      (node (ref "X2") (pin "3") (pinfunction "1_3") (pintype "passive"))
      (node (ref "X2") (pin "4") (pinfunction "1_4") (pintype "passive"))
    )
    (net (code "69") (name "/VREF_Y") (class "Default")
      (node (ref "C16") (pin "1") (pinfunction "1_1") (pintype "passive"))
      (node (ref "R24") (pin "1") (pinfunction "1_1") (pintype "passive"))
      (node (ref "U14") (pin "12") (pinfunction "AVREF_12") (pintype "input"))
      (node (ref "U14") (pin "13") (pinfunction "BVREF_13") (pintype "input"))
    )
    (net (code "70") (name "GND") (class "Default")
      (node (ref "C11") (pin "2") (pinfunction "2_2") (pintype "passive"))
      (node (ref "C12") (pin "2") (pinfunction "2_2") (pintype "passive"))
      (node (ref "C13") (pin "2") (pinfunction "2_2") (pintype "passive"))
      (node (ref "C14") (pin "2") (pinfunction "2_2") (pintype "passive"))
      (node (ref "C15") (pin "2") (pinfunction "2_2") (pintype "passive"))
      (node (ref "C16") (pin "2") (pinfunction "2_2") (pintype "passive"))
      (node (ref "C17") (pin "2") (pinfunction "2_2") (pintype "passive"))
      (node (ref "C18") (pin "2") (pinfunction "2_2") (pintype "passive"))
      (node (ref "C19") (pin "2") (pinfunction "2_2") (pintype "passive"))
      (node (ref "C26") (pin "2") (pinfunction "2_2") (pintype "passive"))
      (node (ref "C27") (pin "2") (pinfunction "2_2") (pintype "passive"))
      (node (ref "C28") (pin "2") (pinfunction "2_2") (pintype "passive"))
      (node (ref "C29") (pin "2") (pinfunction "2_2") (pintype "passive"))
      (node (ref "C30") (pin "2") (pinfunction "2_2") (pintype "passive"))
      (node (ref "C31") (pin "2") (pinfunction "2_2") (pintype "passive"))
      (node (ref "C32") (pin "2") (pinfunction "2_2") (pintype "passive"))
      (node (ref "C33") (pin "2") (pinfunction "2_2") (pintype "passive"))
      (node (ref "C34") (pin "2") (pinfunction "2_2") (pintype "passive"))
      (node (ref "C35") (pin "2") (pinfunction "2_2") (pintype "passive"))
      (node (ref "C36") (pin "2") (pinfunction "2_2") (pintype "passive"))
      (node (ref "C37") (pin "2") (pinfunction "2_2") (pintype "passive"))
      (node (ref "C38") (pin "2") (pinfunction "2_2") (pintype "passive"))
      (node (ref "C39") (pin "2") (pinfunction "2_2") (pintype "passive"))
      (node (ref "C40") (pin "2") (pinfunction "2_2") (pintype "passive"))
      (node (ref "C41") (pin "2") (pinfunction "2_2") (pintype "passive"))
      (node (ref "C42") (pin "2") (pinfunction "2_2") (pintype "passive"))
      (node (ref "C43") (pin "2") (pinfunction "2_2") (pintype "passive"))
      (node (ref "C44") (pin "2") (pinfunction "2_2") (pintype "passive"))
      (node (ref "C45") (pin "2") (pinfunction "2_2") (pintype "passive"))
      (node (ref "C46") (pin "2") (pinfunction "2_2") (pintype "passive"))
      (node (ref "C47") (pin "2") (pinfunction "2_2") (pintype "passive"))
      (node (ref "C48") (pin "2") (pinfunction "2_2") (pintype "passive"))
      (node (ref "C49") (pin "2") (pinfunction "2_2") (pintype "passive"))
      (node (ref "C50") (pin "2") (pinfunction "2_2") (pintype "passive"))
      (node (ref "C52") (pin "2") (pinfunction "2_2") (pintype "passive"))
      (node (ref "C53") (pin "2") (pinfunction "2_2") (pintype "passive"))
      (node (ref "C54") (pin "2") (pinfunction "2_2") (pintype "passive"))
      (node (ref "C57") (pin "2") (pinfunction "2_2") (pintype "passive"))
      (node (ref "C58") (pin "2") (pinfunction "2_2") (pintype "passive"))
      (node (ref "C59") (pin "2") (pinfunction "2_2") (pintype "passive"))
      (node (ref "C61") (pin "2") (pinfunction "2_2") (pintype "passive"))
      (node (ref "D4") (pin "A") (pinfunction "A_A") (pintype "passive"))
      (node (ref "D5") (pin "A") (pinfunction "A_A") (pintype "passive"))
      (node (ref "IC6") (pin "3") (pinfunction "GND_3") (pintype "power_in"))
      (node (ref "IC7") (pin "3") (pinfunction "GND_3") (pintype "power_in"))
      (node (ref "LED4") (pin "C") (pinfunction "C_C") (pintype "passive"))
      (node (ref "P8") (pin "1") (pinfunction "1_1") (pintype "passive"))
      (node (ref "P8") (pin "2") (pinfunction "2_2") (pintype "passive"))
      (node (ref "P9") (pin "1") (pinfunction "1_1") (pintype "passive"))
      (node (ref "P9") (pin "2") (pinfunction "2_2") (pintype "passive"))
      (node (ref "P9") (pin "43") (pinfunction "43_43") (pintype "passive"))
      (node (ref "P9") (pin "44") (pinfunction "44_44") (pintype "passive"))
      (node (ref "P9") (pin "45") (pinfunction "45_45") (pintype "passive"))
      (node (ref "P9") (pin "46") (pinfunction "46_46") (pintype "passive"))
      (node (ref "Q1") (pin "1") (pinfunction "S_1") (pintype "passive"))
      (node (ref "Q1") (pin "2") (pinfunction "S_2") (pintype "passive"))
      (node (ref "Q1") (pin "3") (pinfunction "S_3") (pintype "passive"))
      (node (ref "Q2") (pin "1") (pinfunction "S_1") (pintype "passive"))
      (node (ref "Q2") (pin "2") (pinfunction "S_2") (pintype "passive"))
      (node (ref "Q2") (pin "3") (pinfunction "S_3") (pintype "passive"))
      (node (ref "Q3") (pin "1") (pinfunction "S_1") (pintype "passive"))
      (node (ref "Q3") (pin "2") (pinfunction "S_2") (pintype "passive"))
      (node (ref "Q3") (pin "3") (pinfunction "S_3") (pintype "passive"))
      (node (ref "Q4") (pin "2") (pinfunction "E_2") (pintype "passive"))
      (node (ref "Q5") (pin "2") (pinfunction "E_2") (pintype "passive"))
      (node (ref "Q6") (pin "2") (pinfunction "E_2") (pintype "passive"))
      (node (ref "Q7") (pin "2") (pinfunction "E_2") (pintype "passive"))
      (node (ref "R1") (pin "1") (pinfunction "1_1") (pintype "passive"))
      (node (ref "R10") (pin "1") (pinfunction "1_1") (pintype "passive"))
      (node (ref "R2") (pin "1") (pinfunction "1_1") (pintype "passive"))
      (node (ref "R3") (pin "1") (pinfunction "1_1") (pintype "passive"))
      (node (ref "R4") (pin "1") (pinfunction "1_1") (pintype "passive"))
      (node (ref "R43") (pin "2") (pinfunction "2_2") (pintype "passive"))
      (node (ref "R44") (pin "2") (pinfunction "2_2") (pintype "passive"))
      (node (ref "R46") (pin "1") (pinfunction "1_1") (pintype "passive"))
      (node (ref "R47") (pin "1") (pinfunction "1_1") (pintype "passive"))
      (node (ref "R48") (pin "1") (pinfunction "1_1") (pintype "passive"))
      (node (ref "R5") (pin "1") (pinfunction "1_1") (pintype "passive"))
      (node (ref "R6") (pin "1") (pinfunction "1_1") (pintype "passive"))
      (node (ref "R7") (pin "1") (pinfunction "1_1") (pintype "passive"))
      (node (ref "R8") (pin "1") (pinfunction "1_1") (pintype "passive"))
      (node (ref "R9") (pin "1") (pinfunction "1_1") (pintype "passive"))
      (node (ref "U1") (pin "13") (pinfunction "~{OE}_13") (pintype "input"))
      (node (ref "U1") (pin "8") (pinfunction "GND_8") (pintype "passive"))
      (node (ref "U10") (pin "6") (pinfunction "GND_6") (pintype "power_in"))
      (node (ref "U10") (pin "EP") (pinfunction "EP_EP") (pintype "power_in"))
      (node (ref "U11") (pin "14") (pinfunction "VSS_14") (pintype "passive"))
      (node (ref "U13") (pin "14") (pinfunction "GND_0_14") (pintype "power_in"))
      (node (ref "U13") (pin "28") (pinfunction "GND_1_28") (pintype "power_in"))
      (node (ref "U13") (pin "EXP") (pinfunction "GND_PAD_EXP") (pintype "power_in"))
      (node (ref "U14") (pin "14") (pinfunction "GND_0_14") (pintype "power_in"))
      (node (ref "U14") (pin "28") (pinfunction "GND_1_28") (pintype "power_in"))
      (node (ref "U14") (pin "EXP") (pinfunction "GND_PAD_EXP") (pintype "power_in"))
      (node (ref "U15") (pin "14") (pinfunction "GND_0_14") (pintype "power_in"))
      (node (ref "U15") (pin "28") (pinfunction "GND_1_28") (pintype "power_in"))
      (node (ref "U15") (pin "EXP") (pinfunction "GND_PAD_EXP") (pintype "power_in"))
      (node (ref "U16") (pin "14") (pinfunction "GND_0_14") (pintype "power_in"))
      (node (ref "U16") (pin "28") (pinfunction "GND_1_28") (pintype "power_in"))
      (node (ref "U16") (pin "EXP") (pinfunction "GND_PAD_EXP") (pintype "power_in"))
      (node (ref "U17") (pin "14") (pinfunction "GND_0_14") (pintype "power_in"))
      (node (ref "U17") (pin "28") (pinfunction "GND_1_28") (pintype "power_in"))
      (node (ref "U17") (pin "EXP") (pinfunction "GND_PAD_EXP") (pintype "power_in"))
      (node (ref "U18") (pin "1") (pinfunction "A0_1") (pintype "input"))
      (node (ref "U18") (pin "2") (pinfunction "A1_2") (pintype "input"))
      (node (ref "U18") (pin "4") (pinfunction "GND_4") (pintype "power_in"))
      (node (ref "U19") (pin "8") (pinfunction "VSS_8") (pintype "power_in"))
      (node (ref "U2") (pin "13") (pinfunction "~{OE}_13") (pintype "input"))
      (node (ref "U2") (pin "8") (pinfunction "GND_8") (pintype "passive"))
      (node (ref "U3") (pin "13") (pinfunction "~{OE}_13") (pintype "input"))
      (node (ref "U3") (pin "8") (pinfunction "GND_8") (pintype "passive"))
      (node (ref "U4") (pin "13") (pinfunction "~{OE}_13") (pintype "input"))
      (node (ref "U4") (pin "8") (pinfunction "GND_8") (pintype "passive"))
      (node (ref "U5") (pin "13") (pinfunction "~{OE}_13") (pintype "input"))
      (node (ref "U5") (pin "8") (pinfunction "GND_8") (pintype "passive"))
      (node (ref "U6") (pin "14") (pinfunction "PGND_14") (pintype "power_in"))
      (node (ref "U6") (pin "15") (pinfunction "PGND_15") (pintype "power_in"))
      (node (ref "U6") (pin "4") (pinfunction "SGND_4") (pintype "power_in"))
      (node (ref "U6") (pin "P$17") (pinfunction "EP_P$17") (pintype "power_in"))
      (node (ref "X1") (pin "3") (pinfunction "S_3") (pintype "passive"))
      (node (ref "X10") (pin "3") (pinfunction "S_3") (pintype "passive"))
      (node (ref "X11") (pin "1") (pinfunction "S_1") (pintype "passive"))
      (node (ref "X12") (pin "3") (pinfunction "S_3") (pintype "passive"))
      (node (ref "X13") (pin "3") (pinfunction "S_3") (pintype "passive"))
      (node (ref "X19") (pin "3") (pinfunction "S_3") (pintype "passive"))
      (node (ref "X2") (pin "1") (pinfunction "1_1") (pintype "passive"))
      (node (ref "X2") (pin "2") (pinfunction "1_2") (pintype "passive"))
      (node (ref "X22") (pin "3") (pinfunction "S_3") (pintype "passive"))
      (node (ref "X7") (pin "1") (pinfunction "S_1") (pintype "passive"))
      (node (ref "X8") (pin "1") (pinfunction "S_1") (pintype "passive"))
    )
    (net (code "71") (name "Net-(C51-Pad1)") (class "Default")
      (node (ref "C51") (pin "1") (pinfunction "1_1") (pintype "passive"))
      (node (ref "R58") (pin "1") (pinfunction "1_1") (pintype "passive"))
    )
    (net (code "72") (name "Net-(C56-Pad2)") (class "Default")
      (node (ref "C56") (pin "2") (pinfunction "2_2") (pintype "passive"))
      (node (ref "R44") (pin "1") (pinfunction "1_1") (pintype "passive"))
    )
    (net (code "73") (name "Net-(L1-1)") (class "Default")
      (node (ref "C51") (pin "2") (pinfunction "2_2") (pintype "passive"))
      (node (ref "L1") (pin "P$1") (pinfunction "1_P$1") (pintype "passive"))
      (node (ref "U6") (pin "1") (pinfunction "SW_1") (pintype "power_in"))
      (node (ref "U6") (pin "12") (pinfunction "SW_12") (pintype "power_in"))
      (node (ref "U6") (pin "13") (pinfunction "SW_13") (pintype "power_in"))
      (node (ref "U6") (pin "16") (pinfunction "SW_16") (pintype "power_in"))
    )
    (net (code "74") (name "Net-(LED1-PadA)") (class "Default")
      (node (ref "LED1") (pin "A") (pinfunction "A_A") (pintype "passive"))
      (node (ref "R14") (pin "1") (pinfunction "1_1") (pintype "passive"))
    )
    (net (code "75") (name "Net-(LED2-PadA)") (class "Default")
      (node (ref "LED2") (pin "A") (pinfunction "A_A") (pintype "passive"))
      (node (ref "R16") (pin "1") (pinfunction "1_1") (pintype "passive"))
    )
    (net (code "76") (name "Net-(LED3-PadA)") (class "Default")
      (node (ref "LED3") (pin "A") (pinfunction "A_A") (pintype "passive"))
      (node (ref "R15") (pin "1") (pinfunction "1_1") (pintype "passive"))
    )
    (net (code "77") (name "Net-(LED4-PadA)") (class "Default")
      (node (ref "LED4") (pin "A") (pinfunction "A_A") (pintype "passive"))
      (node (ref "R11") (pin "1") (pinfunction "1_1") (pintype "passive"))
    )
    (net (code "78") (name "Net-(LED5-PadA)") (class "Default")
      (node (ref "LED5") (pin "A") (pinfunction "A_A") (pintype "passive"))
      (node (ref "R19") (pin "1") (pinfunction "1_1") (pintype "passive"))
    )
    (net (code "79") (name "Net-(LED6-PadA)") (class "Default")
      (node (ref "LED6") (pin "A") (pinfunction "A_A") (pintype "passive"))
      (node (ref "R20") (pin "1") (pinfunction "1_1") (pintype "passive"))
    )
    (net (code "80") (name "Net-(LED7-PadA)") (class "Default")
      (node (ref "LED7") (pin "A") (pinfunction "A_A") (pintype "passive"))
      (node (ref "R21") (pin "1") (pinfunction "1_1") (pintype "passive"))
    )
    (net (code "81") (name "Net-(LED8-PadC)") (class "Default")
      (node (ref "LED8") (pin "C") (pinfunction "C_C") (pintype "passive"))
      (node (ref "R45") (pin "2") (pinfunction "2_2") (pintype "passive"))
    )
    (net (code "82") (name "Net-(LED9-PadA)") (class "Default")
      (node (ref "LED9") (pin "A") (pinfunction "A_A") (pintype "passive"))
      (node (ref "R25") (pin "1") (pinfunction "1_1") (pintype "passive"))
    )
    (net (code "83") (name "Net-(Q1-G)") (class "Default")
      (node (ref "Q1") (pin "4") (pinfunction "G_4") (pintype "passive"))
      (node (ref "R31") (pin "1") (pinfunction "1_1") (pintype "passive"))
    )
    (net (code "84") (name "Net-(Q2-G)") (class "Default")
      (node (ref "Q2") (pin "4") (pinfunction "G_4") (pintype "passive"))
      (node (ref "R37") (pin "1") (pinfunction "1_1") (pintype "passive"))
    )
    (net (code "85") (name "Net-(Q3-G)") (class "Default")
      (node (ref "Q3") (pin "4") (pinfunction "G_4") (pintype "passive"))
      (node (ref "R32") (pin "1") (pinfunction "1_1") (pintype "passive"))
    )
    (net (code "86") (name "Net-(Q4-B)") (class "Default")
      (node (ref "Q4") (pin "1") (pinfunction "B_1") (pintype "passive"))
      (node (ref "R73") (pin "1") (pinfunction "1_1") (pintype "passive"))
    )
    (net (code "87") (name "Net-(Q4-C)") (class "Default")
      (node (ref "LED6") (pin "C") (pinfunction "C_C") (pintype "passive"))
      (node (ref "Q4") (pin "3") (pinfunction "C_3") (pintype "passive"))
      (node (ref "X5") (pin "2") (pinfunction "S_2") (pintype "passive"))
    )
    (net (code "88") (name "Net-(Q5-C)") (class "Default")
      (node (ref "LED7") (pin "C") (pinfunction "C_C") (pintype "passive"))
      (node (ref "Q5") (pin "3") (pinfunction "C_3") (pintype "passive"))
      (node (ref "X6") (pin "2") (pinfunction "S_2") (pintype "passive"))
    )
    (net (code "89") (name "Net-(Q6-C)") (class "Default")
      (node (ref "LED9") (pin "C") (pinfunction "C_C") (pintype "passive"))
      (node (ref "Q6") (pin "3") (pinfunction "C_3") (pintype "passive"))
      (node (ref "X9") (pin "2") (pinfunction "S_2") (pintype "passive"))
    )
    (net (code "90") (name "Net-(Q7-C)") (class "Default")
      (node (ref "LED5") (pin "C") (pinfunction "C_C") (pintype "passive"))
      (node (ref "Q7") (pin "3") (pinfunction "C_3") (pintype "passive"))
      (node (ref "X4") (pin "2") (pinfunction "S_2") (pintype "passive"))
    )
    (net (code "91") (name "Net-(U1-QB)") (class "Default")
      (node (ref "U1") (pin "1") (pinfunction "QB_1") (pintype "output"))
      (node (ref "U13") (pin "26") (pinfunction "MODE2_26") (pintype "input"))
    )
    (net (code "92") (name "Net-(U1-QC)") (class "Default")
      (node (ref "U1") (pin "2") (pinfunction "QC_2") (pintype "output"))
      (node (ref "U13") (pin "25") (pinfunction "MODE1_25") (pintype "input"))
    )
    (net (code "93") (name "Net-(U1-QD)") (class "Default")
      (node (ref "U1") (pin "3") (pinfunction "QD_3") (pintype "output"))
      (node (ref "U13") (pin "24") (pinfunction "MODE0_24") (pintype "input"))
    )
    (net (code "94") (name "Net-(U1-QE)") (class "Default")
      (node (ref "R29") (pin "2") (pinfunction "2_2") (pintype "passive"))
      (node (ref "U1") (pin "4") (pinfunction "QE_4") (pintype "output"))
    )
    (net (code "95") (name "Net-(U1-QF)") (class "Default")
      (node (ref "R28") (pin "2") (pinfunction "2_2") (pintype "passive"))
      (node (ref "U1") (pin "5") (pinfunction "QF_5") (pintype "output"))
    )
    (net (code "96") (name "Net-(U1-QG)") (class "Default")
      (node (ref "U1") (pin "6") (pinfunction "QG_6") (pintype "output"))
      (node (ref "U13") (pin "17") (pinfunction "SLEEP_17") (pintype "input"))
    )
    (net (code "97") (name "Net-(U1-QH)") (class "Default")
      (node (ref "U1") (pin "7") (pinfunction "QH_7") (pintype "output"))
      (node (ref "U13") (pin "16") (pinfunction "RESET_16") (pintype "input"))
    )
    (net (code "98") (name "Net-(U1-~{SRCLR})") (class "Default")
      (node (ref "R12") (pin "1") (pinfunction "1_1") (pintype "passive"))
      (node (ref "U1") (pin "10") (pinfunction "~{SRCLR}_10") (pintype "input"))
    )
    (net (code "99") (name "Net-(U2-QE)") (class "Default")
      (node (ref "R71") (pin "2") (pinfunction "2_2") (pintype "passive"))
      (node (ref "U2") (pin "4") (pinfunction "QE_4") (pintype "output"))
    )
    (net (code "100") (name "Net-(U2-QF)") (class "Default")
      (node (ref "R70") (pin "2") (pinfunction "2_2") (pintype "passive"))
      (node (ref "U2") (pin "5") (pinfunction "QF_5") (pintype "output"))
    )
    (net (code "101") (name "Net-(U2-~{SRCLR})") (class "Default")
      (node (ref "R35") (pin "1") (pinfunction "1_1") (pintype "passive"))
      (node (ref "U2") (pin "10") (pinfunction "~{SRCLR}_10") (pintype "input"))
    )
    (net (code "102") (name "Net-(U3-QE)") (class "Default")
      (node (ref "R27") (pin "2") (pinfunction "2_2") (pintype "passive"))
      (node (ref "U3") (pin "4") (pinfunction "QE_4") (pintype "output"))
    )
    (net (code "103") (name "Net-(U3-QF)") (class "Default")
      (node (ref "R26") (pin "2") (pinfunction "2_2") (pintype "passive"))
      (node (ref "U3") (pin "5") (pinfunction "QF_5") (pintype "output"))
    )
    (net (code "104") (name "Net-(U3-~{SRCLR})") (class "Default")
      (node (ref "R36") (pin "1") (pinfunction "1_1") (pintype "passive"))
      (node (ref "U3") (pin "10") (pinfunction "~{SRCLR}_10") (pintype "input"))
    )
    (net (code "105") (name "Net-(U4-QE)") (class "Default")
      (node (ref "R67") (pin "2") (pinfunction "2_2") (pintype "passive"))
      (node (ref "U4") (pin "4") (pinfunction "QE_4") (pintype "output"))
    )
    (net (code "106") (name "Net-(U4-QF)") (class "Default")
      (node (ref "R30") (pin "2") (pinfunction "2_2") (pintype "passive"))
      (node (ref "U4") (pin "5") (pinfunction "QF_5") (pintype "output"))
    )
    (net (code "107") (name "Net-(U4-~{SRCLR})") (class "Default")
      (node (ref "R33") (pin "1") (pinfunction "1_1") (pintype "passive"))
      (node (ref "U4") (pin "10") (pinfunction "~{SRCLR}_10") (pintype "input"))
    )
    (net (code "108") (name "Net-(U5-QE)") (class "Default")
      (node (ref "R69") (pin "2") (pinfunction "2_2") (pintype "passive"))
      (node (ref "U5") (pin "4") (pinfunction "QE_4") (pintype "output"))
    )
    (net (code "109") (name "Net-(U5-QF)") (class "Default")
      (node (ref "R68") (pin "2") (pinfunction "2_2") (pintype "passive"))
      (node (ref "U5") (pin "5") (pinfunction "QF_5") (pintype "output"))
    )
    (net (code "110") (name "Net-(U5-~{SRCLR})") (class "Default")
      (node (ref "R34") (pin "1") (pinfunction "1_1") (pintype "passive"))
      (node (ref "U5") (pin "10") (pinfunction "~{SRCLR}_10") (pintype "input"))
    )
    (net (code "111") (name "Net-(U6-BOOST)") (class "Default")
      (node (ref "R58") (pin "2") (pinfunction "2_2") (pintype "passive"))
      (node (ref "U6") (pin "10") (pinfunction "BOOST_10") (pintype "bidirectional"))
    )
    (net (code "112") (name "Net-(U6-PG)") (class "Default")
      (node (ref "R41") (pin "1") (pinfunction "1_1") (pintype "passive"))
      (node (ref "U6") (pin "8") (pinfunction "PG_8") (pintype "output"))
    )
    (net (code "113") (name "Net-(U10-BOOT)") (class "Default")
      (node (ref "C55") (pin "1") (pinfunction "1_1") (pintype "passive"))
      (node (ref "U10") (pin "2") (pinfunction "BOOT_2") (pintype "input"))
    )
    (net (code "114") (name "Net-(U10-COMP)") (class "Default")
      (node (ref "C56") (pin "1") (pinfunction "1_1") (pintype "passive"))
      (node (ref "U10") (pin "8") (pinfunction "COMP_8") (pintype "bidirectional"))
    )
    (net (code "115") (name "Net-(U10-FB)") (class "Default")
      (node (ref "R42") (pin "2") (pinfunction "2_2") (pintype "passive"))
      (node (ref "R43") (pin "1") (pinfunction "1_1") (pintype "passive"))
      (node (ref "U10") (pin "7") (pinfunction "FB_7") (pintype "input"))
    )
    (net (code "116") (name "Net-(U10-SS)") (class "Default")
      (node (ref "C54") (pin "1") (pinfunction "1_1") (pintype "passive"))
      (node (ref "U10") (pin "10") (pinfunction "SS_10") (pintype "bidirectional"))
    )
    (net (code "117") (name "Net-(U10-SW)") (class "Default")
      (node (ref "C55") (pin "2") (pinfunction "2_2") (pintype "passive"))
      (node (ref "D4") (pin "C") (pinfunction "C_C") (pintype "passive"))
      (node (ref "L2") (pin "P$2") (pinfunction "P$2_P$2") (pintype "passive"))
      (node (ref "U10") (pin "5") (pinfunction "SW_5") (pintype "power_in"))
    )
    (net (code "118") (name "Net-(U13-AOUT1)") (class "Default")
      (node (ref "U13") (pin "5") (pinfunction "AOUT1_5") (pintype "output"))
      (node (ref "X14") (pin "4") (pinfunction "S_4") (pintype "passive"))
    )
    (net (code "119") (name "Net-(U13-AOUT2)") (class "Default")
      (node (ref "U13") (pin "7") (pinfunction "AOUT2_7") (pintype "output"))
      (node (ref "X14") (pin "3") (pinfunction "S_3") (pintype "passive"))
    )
    (net (code "120") (name "Net-(U13-AVREF)") (class "Default")
      (node (ref "C12") (pin "1") (pinfunction "1_1") (pintype "passive"))
      (node (ref "R49") (pin "1") (pinfunction "1_1") (pintype "passive"))
      (node (ref "U13") (pin "12") (pinfunction "AVREF_12") (pintype "input"))
      (node (ref "U13") (pin "13") (pinfunction "BVREF_13") (pintype "input"))
    )
    (net (code "121") (name "Net-(U13-BOUT1)") (class "Default")
      (node (ref "U13") (pin "10") (pinfunction "BOUT1_10") (pintype "output"))
      (node (ref "X14") (pin "1") (pinfunction "S_1") (pintype "passive"))
    )
    (net (code "122") (name "Net-(U13-BOUT2)") (class "Default")
      (node (ref "U13") (pin "8") (pinfunction "BOUT2_8") (pintype "output"))
      (node (ref "X14") (pin "2") (pinfunction "S_2") (pintype "passive"))
    )
    (net (code "123") (name "Net-(U13-CP1)") (class "Default")
      (node (ref "C1") (pin "2") (pinfunction "2_2") (pintype "passive"))
      (node (ref "U13") (pin "1") (pinfunction "CP1_1") (pintype "bidirectional"))
    )
    (net (code "124") (name "Net-(U13-CP2)") (class "Default")
      (node (ref "C1") (pin "1") (pinfunction "1_1") (pintype "passive"))
      (node (ref "U13") (pin "2") (pinfunction "CP2_2") (pintype "bidirectional"))
    )
    (net (code "125") (name "Net-(U13-DECAY)") (class "Default")
      (node (ref "R28") (pin "1") (pinfunction "1_1") (pintype "passive"))
      (node (ref "R29") (pin "1") (pinfunction "1_1") (pintype "passive"))
      (node (ref "U13") (pin "19") (pinfunction "DECAY_19") (pintype "input"))
    )
    (net (code "126") (name "Net-(U13-ISENA)") (class "Default")
      (node (ref "R2") (pin "2") (pinfunction "2_2") (pintype "passive"))
      (node (ref "U13") (pin "6") (pinfunction "ISENA_6") (pintype "output"))
    )
    (net (code "127") (name "Net-(U13-ISENB)") (class "Default")
      (node (ref "R1") (pin "2") (pinfunction "2_2") (pintype "passive"))
      (node (ref "U13") (pin "9") (pinfunction "ISENB_9") (pintype "output"))
    )
    (net (code "128") (name "Net-(U13-VCP)") (class "Default")
      (node (ref "C2") (pin "2") (pinfunction "2_2") (pintype "passive"))
      (node (ref "R63") (pin "2") (pinfunction "2_2") (pintype "passive"))
      (node (ref "U13") (pin "3") (pinfunction "VCP_3") (pintype "bidirectional"))
    )
    (net (code "129") (name "Net-(U14-AOUT1)") (class "Default")
      (node (ref "U14") (pin "5") (pinfunction "AOUT1_5") (pintype "output"))
      (node (ref "X15") (pin "4") (pinfunction "S_4") (pintype "passive"))
    )
    (net (code "130") (name "Net-(U14-AOUT2)") (class "Default")
      (node (ref "U14") (pin "7") (pinfunction "AOUT2_7") (pintype "output"))
      (node (ref "X15") (pin "3") (pinfunction "S_3") (pintype "passive"))
    )
    (net (code "131") (name "Net-(U14-BOUT1)") (class "Default")
      (node (ref "U14") (pin "10") (pinfunction "BOUT1_10") (pintype "output"))
      (node (ref "X15") (pin "1") (pinfunction "S_1") (pintype "passive"))
    )
    (net (code "132") (name "Net-(U14-BOUT2)") (class "Default")
      (node (ref "U14") (pin "8") (pinfunction "BOUT2_8") (pintype "output"))
      (node (ref "X15") (pin "2") (pinfunction "S_2") (pintype "passive"))
    )
    (net (code "133") (name "Net-(U14-CP1)") (class "Default")
      (node (ref "C3") (pin "2") (pinfunction "2_2") (pintype "passive"))
      (node (ref "U14") (pin "1") (pinfunction "CP1_1") (pintype "bidirectional"))
    )
    (net (code "134") (name "Net-(U14-CP2)") (class "Default")
      (node (ref "C3") (pin "1") (pinfunction "1_1") (pintype "passive"))
      (node (ref "U14") (pin "2") (pinfunction "CP2_2") (pintype "bidirectional"))
    )
    (net (code "135") (name "Net-(U14-DECAY)") (class "Default")
      (node (ref "R70") (pin "1") (pinfunction "1_1") (pintype "passive"))
      (node (ref "R71") (pin "1") (pinfunction "1_1") (pintype "passive"))
      (node (ref "U14") (pin "19") (pinfunction "DECAY_19") (pintype "input"))
    )
    (net (code "136") (name "Net-(U14-ISENA)") (class "Default")
      (node (ref "R4") (pin "2") (pinfunction "2_2") (pintype "passive"))
      (node (ref "U14") (pin "6") (pinfunction "ISENA_6") (pintype "output"))
    )
    (net (code "137") (name "Net-(U14-ISENB)") (class "Default")
      (node (ref "R3") (pin "2") (pinfunction "2_2") (pintype "passive"))
      (node (ref "U14") (pin "9") (pinfunction "ISENB_9") (pintype "output"))
    )
    (net (code "138") (name "Net-(U14-MODE0)") (class "Default")
      (node (ref "U14") (pin "24") (pinfunction "MODE0_24") (pintype "input"))
      (node (ref "U2") (pin "3") (pinfunction "QD_3") (pintype "output"))
    )
    (net (code "139") (name "Net-(U14-MODE1)") (class "Default")
      (node (ref "U14") (pin "25") (pinfunction "MODE1_25") (pintype "input"))
      (node (ref "U2") (pin "2") (pinfunction "QC_2") (pintype "output"))
    )
    (net (code "140") (name "Net-(U14-MODE2)") (class "Default")
      (node (ref "U14") (pin "26") (pinfunction "MODE2_26") (pintype "input"))
      (node (ref "U2") (pin "1") (pinfunction "QB_1") (pintype "output"))
    )
    (net (code "141") (name "Net-(U14-RESET)") (class "Default")
      (node (ref "U14") (pin "16") (pinfunction "RESET_16") (pintype "input"))
      (node (ref "U2") (pin "7") (pinfunction "QH_7") (pintype "output"))
    )
    (net (code "142") (name "Net-(U14-SLEEP)") (class "Default")
      (node (ref "U14") (pin "17") (pinfunction "SLEEP_17") (pintype "input"))
      (node (ref "U2") (pin "6") (pinfunction "QG_6") (pintype "output"))
    )
    (net (code "143") (name "Net-(U14-VCP)") (class "Default")
      (node (ref "C4") (pin "2") (pinfunction "2_2") (pintype "passive"))
      (node (ref "R64") (pin "2") (pinfunction "2_2") (pintype "passive"))
      (node (ref "U14") (pin "3") (pinfunction "VCP_3") (pintype "bidirectional"))
    )
    (net (code "144") (name "Net-(U15-AOUT1)") (class "Default")
      (node (ref "U15") (pin "5") (pinfunction "AOUT1_5") (pintype "output"))
      (node (ref "X16") (pin "4") (pinfunction "S_4") (pintype "passive"))
    )
    (net (code "145") (name "Net-(U15-AOUT2)") (class "Default")
      (node (ref "U15") (pin "7") (pinfunction "AOUT2_7") (pintype "output"))
      (node (ref "X16") (pin "3") (pinfunction "S_3") (pintype "passive"))
    )
    (net (code "146") (name "Net-(U15-AVREF)") (class "Default")
      (node (ref "C30") (pin "1") (pinfunction "1_1") (pintype "passive"))
      (node (ref "R50") (pin "1") (pinfunction "1_1") (pintype "passive"))
      (node (ref "U15") (pin "12") (pinfunction "AVREF_12") (pintype "input"))
      (node (ref "U15") (pin "13") (pinfunction "BVREF_13") (pintype "input"))
    )
    (net (code "147") (name "Net-(U15-BOUT1)") (class "Default")
      (node (ref "U15") (pin "10") (pinfunction "BOUT1_10") (pintype "output"))
      (node (ref "X16") (pin "1") (pinfunction "S_1") (pintype "passive"))
    )
    (net (code "148") (name "Net-(U15-BOUT2)") (class "Default")
      (node (ref "U15") (pin "8") (pinfunction "BOUT2_8") (pintype "output"))
      (node (ref "X16") (pin "2") (pinfunction "S_2") (pintype "passive"))
    )
    (net (code "149") (name "Net-(U15-CP1)") (class "Default")
      (node (ref "C5") (pin "2") (pinfunction "2_2") (pintype "passive"))
      (node (ref "U15") (pin "1") (pinfunction "CP1_1") (pintype "bidirectional"))
    )
    (net (code "150") (name "Net-(U15-CP2)") (class "Default")
      (node (ref "C5") (pin "1") (pinfunction "1_1") (pintype "passive"))
      (node (ref "U15") (pin "2") (pinfunction "CP2_2") (pintype "bidirectional"))
    )
    (net (code "151") (name "Net-(U15-DECAY)") (class "Default")
      (node (ref "R26") (pin "1") (pinfunction "1_1") (pintype "passive"))
      (node (ref "R27") (pin "1") (pinfunction "1_1") (pintype "passive"))
      (node (ref "U15") (pin "19") (pinfunction "DECAY_19") (pintype "input"))
    )
    (net (code "152") (name "Net-(U15-ISENA)") (class "Default")
      (node (ref "R6") (pin "2") (pinfunction "2_2") (pintype "passive"))
      (node (ref "U15") (pin "6") (pinfunction "ISENA_6") (pintype "output"))
    )
    (net (code "153") (name "Net-(U15-ISENB)") (class "Default")
      (node (ref "R5") (pin "2") (pinfunction "2_2") (pintype "passive"))
      (node (ref "U15") (pin "9") (pinfunction "ISENB_9") (pintype "output"))
    )
    (net (code "154") (name "Net-(U15-MODE0)") (class "Default")
      (node (ref "U15") (pin "24") (pinfunction "MODE0_24") (pintype "input"))
      (node (ref "U3") (pin "3") (pinfunction "QD_3") (pintype "output"))
    )
    (net (code "155") (name "Net-(U15-MODE1)") (class "Default")
      (node (ref "U15") (pin "25") (pinfunction "MODE1_25") (pintype "input"))
      (node (ref "U3") (pin "2") (pinfunction "QC_2") (pintype "output"))
    )
    (net (code "156") (name "Net-(U15-MODE2)") (class "Default")
      (node (ref "U15") (pin "26") (pinfunction "MODE2_26") (pintype "input"))
      (node (ref "U3") (pin "1") (pinfunction "QB_1") (pintype "output"))
    )
    (net (code "157") (name "Net-(U15-RESET)") (class "Default")
      (node (ref "U15") (pin "16") (pinfunction "RESET_16") (pintype "input"))
      (node (ref "U3") (pin "7") (pinfunction "QH_7") (pintype "output"))
    )
    (net (code "158") (name "Net-(U15-SLEEP)") (class "Default")
      (node (ref "U15") (pin "17") (pinfunction "SLEEP_17") (pintype "input"))
      (node (ref "U3") (pin "6") (pinfunction "QG_6") (pintype "output"))
    )
    (net (code "159") (name "Net-(U15-VCP)") (class "Default")
      (node (ref "C6") (pin "2") (pinfunction "2_2") (pintype "passive"))
      (node (ref "R62") (pin "2") (pinfunction "2_2") (pintype "passive"))
      (node (ref "U15") (pin "3") (pinfunction "VCP_3") (pintype "bidirectional"))
    )
    (net (code "160") (name "Net-(U16-AOUT1)") (class "Default")
      (node (ref "U16") (pin "5") (pinfunction "AOUT1_5") (pintype "output"))
      (node (ref "X17") (pin "4") (pinfunction "S_4") (pintype "passive"))
    )
    (net (code "161") (name "Net-(U16-AOUT2)") (class "Default")
      (node (ref "U16") (pin "7") (pinfunction "AOUT2_7") (pintype "output"))
      (node (ref "X17") (pin "3") (pinfunction "S_3") (pintype "passive"))
    )
    (net (code "162") (name "Net-(U16-AVREF)") (class "Default")
      (node (ref "C32") (pin "1") (pinfunction "1_1") (pintype "passive"))
      (node (ref "R51") (pin "1") (pinfunction "1_1") (pintype "passive"))
      (node (ref "U16") (pin "12") (pinfunction "AVREF_12") (pintype "input"))
      (node (ref "U16") (pin "13") (pinfunction "BVREF_13") (pintype "input"))
    )
    (net (code "163") (name "Net-(U16-BOUT1)") (class "Default")
      (node (ref "U16") (pin "10") (pinfunction "BOUT1_10") (pintype "output"))
      (node (ref "X17") (pin "1") (pinfunction "S_1") (pintype "passive"))
    )
    (net (code "164") (name "Net-(U16-BOUT2)") (class "Default")
      (node (ref "U16") (pin "8") (pinfunction "BOUT2_8") (pintype "output"))
      (node (ref "X17") (pin "2") (pinfunction "S_2") (pintype "passive"))
    )
    (net (code "165") (name "Net-(U16-CP1)") (class "Default")
      (node (ref "C7") (pin "2") (pinfunction "2_2") (pintype "passive"))
      (node (ref "U16") (pin "1") (pinfunction "CP1_1") (pintype "bidirectional"))
    )
    (net (code "166") (name "Net-(U16-CP2)") (class "Default")
      (node (ref "C7") (pin "1") (pinfunction "1_1") (pintype "passive"))
      (node (ref "U16") (pin "2") (pinfunction "CP2_2") (pintype "bidirectional"))
    )
    (net (code "167") (name "Net-(U16-DECAY)") (class "Default")
      (node (ref "R30") (pin "1") (pinfunction "1_1") (pintype "passive"))
      (node (ref "R67") (pin "1") (pinfunction "1_1") (pintype "passive"))
      (node (ref "U16") (pin "19") (pinfunction "DECAY_19") (pintype "input"))
    )
    (net (code "168") (name "Net-(U16-ISENA)") (class "Default")
      (node (ref "R8") (pin "2") (pinfunction "2_2") (pintype "passive"))
      (node (ref "U16") (pin "6") (pinfunction "ISENA_6") (pintype "output"))
    )
    (net (code "169") (name "Net-(U16-ISENB)") (class "Default")
      (node (ref "R7") (pin "2") (pinfunction "2_2") (pintype "passive"))
      (node (ref "U16") (pin "9") (pinfunction "ISENB_9") (pintype "output"))
    )
    (net (code "170") (name "Net-(U16-MODE0)") (class "Default")
      (node (ref "U16") (pin "24") (pinfunction "MODE0_24") (pintype "input"))
      (node (ref "U4") (pin "3") (pinfunction "QD_3") (pintype "output"))
    )
    (net (code "171") (name "Net-(U16-MODE1)") (class "Default")
      (node (ref "U16") (pin "25") (pinfunction "MODE1_25") (pintype "input"))
      (node (ref "U4") (pin "2") (pinfunction "QC_2") (pintype "output"))
    )
    (net (code "172") (name "Net-(U16-MODE2)") (class "Default")
      (node (ref "U16") (pin "26") (pinfunction "MODE2_26") (pintype "input"))
      (node (ref "U4") (pin "1") (pinfunction "QB_1") (pintype "output"))
    )
    (net (code "173") (name "Net-(U16-RESET)") (class "Default")
      (node (ref "U16") (pin "16") (pinfunction "RESET_16") (pintype "input"))
      (node (ref "U4") (pin "7") (pinfunction "QH_7") (pintype "output"))
    )
    (net (code "174") (name "Net-(U16-SLEEP)") (class "Default")
      (node (ref "U16") (pin "17") (pinfunction "SLEEP_17") (pintype "input"))
      (node (ref "U4") (pin "6") (pinfunction "QG_6") (pintype "output"))
    )
    (net (code "175") (name "Net-(U16-VCP)") (class "Default")
      (node (ref "C8") (pin "2") (pinfunction "2_2") (pintype "passive"))
      (node (ref "R61") (pin "2") (pinfunction "2_2") (pintype "passive"))
      (node (ref "U16") (pin "3") (pinfunction "VCP_3") (pintype "bidirectional"))
    )
    (net (code "176") (name "Net-(U17-AOUT1)") (class "Default")
      (node (ref "U17") (pin "5") (pinfunction "AOUT1_5") (pintype "output"))
      (node (ref "X18") (pin "4") (pinfunction "S_4") (pintype "passive"))
    )
    (net (code "177") (name "Net-(U17-AOUT2)") (class "Default")
      (node (ref "U17") (pin "7") (pinfunction "AOUT2_7") (pintype "output"))
      (node (ref "X18") (pin "3") (pinfunction "S_3") (pintype "passive"))
    )
    (net (code "178") (name "Net-(U17-AVREF)") (class "Default")
      (node (ref "C34") (pin "1") (pinfunction "1_1") (pintype "passive"))
      (node (ref "R66") (pin "1") (pinfunction "1_1") (pintype "passive"))
      (node (ref "U17") (pin "12") (pinfunction "AVREF_12") (pintype "input"))
      (node (ref "U17") (pin "13") (pinfunction "BVREF_13") (pintype "input"))
    )
    (net (code "179") (name "Net-(U17-BOUT1)") (class "Default")
      (node (ref "U17") (pin "10") (pinfunction "BOUT1_10") (pintype "output"))
      (node (ref "X18") (pin "1") (pinfunction "S_1") (pintype "passive"))
    )
    (net (code "180") (name "Net-(U17-BOUT2)") (class "Default")
      (node (ref "U17") (pin "8") (pinfunction "BOUT2_8") (pintype "output"))
      (node (ref "X18") (pin "2") (pinfunction "S_2") (pintype "passive"))
    )
    (net (code "181") (name "Net-(U17-CP1)") (class "Default")
      (node (ref "C9") (pin "2") (pinfunction "2_2") (pintype "passive"))
      (node (ref "U17") (pin "1") (pinfunction "CP1_1") (pintype "bidirectional"))
    )
    (net (code "182") (name "Net-(U17-CP2)") (class "Default")
      (node (ref "C9") (pin "1") (pinfunction "1_1") (pintype "passive"))
      (node (ref "U17") (pin "2") (pinfunction "CP2_2") (pintype "bidirectional"))
    )
    (net (code "183") (name "Net-(U17-DECAY)") (class "Default")
      (node (ref "R68") (pin "1") (pinfunction "1_1") (pintype "passive"))
      (node (ref "R69") (pin "1") (pinfunction "1_1") (pintype "passive"))
      (node (ref "U17") (pin "19") (pinfunction "DECAY_19") (pintype "input"))
    )
    (net (code "184") (name "Net-(U17-ISENA)") (class "Default")
      (node (ref "R10") (pin "2") (pinfunction "2_2") (pintype "passive"))
      (node (ref "U17") (pin "6") (pinfunction "ISENA_6") (pintype "output"))
    )
    (net (code "185") (name "Net-(U17-ISENB)") (class "Default")
      (node (ref "R9") (pin "2") (pinfunction "2_2") (pintype "passive"))
      (node (ref "U17") (pin "9") (pinfunction "ISENB_9") (pintype "output"))
    )
    (net (code "186") (name "Net-(U17-MODE0)") (class "Default")
      (node (ref "U17") (pin "24") (pinfunction "MODE0_24") (pintype "input"))
      (node (ref "U5") (pin "3") (pinfunction "QD_3") (pintype "output"))
    )
    (net (code "187") (name "Net-(U17-MODE1)") (class "Default")
      (node (ref "U17") (pin "25") (pinfunction "MODE1_25") (pintype "input"))
      (node (ref "U5") (pin "2") (pinfunction "QC_2") (pintype "output"))
    )
    (net (code "188") (name "Net-(U17-MODE2)") (class "Default")
      (node (ref "U17") (pin "26") (pinfunction "MODE2_26") (pintype "input"))
      (node (ref "U5") (pin "1") (pinfunction "QB_1") (pintype "output"))
    )
    (net (code "189") (name "Net-(U17-RESET)") (class "Default")
      (node (ref "U17") (pin "16") (pinfunction "RESET_16") (pintype "input"))
      (node (ref "U5") (pin "7") (pinfunction "QH_7") (pintype "output"))
    )
    (net (code "190") (name "Net-(U17-SLEEP)") (class "Default")
      (node (ref "U17") (pin "17") (pinfunction "SLEEP_17") (pintype "input"))
      (node (ref "U5") (pin "6") (pinfunction "QG_6") (pintype "output"))
    )
    (net (code "191") (name "Net-(U17-VCP)") (class "Default")
      (node (ref "C10") (pin "2") (pinfunction "2_2") (pintype "passive"))
      (node (ref "R65") (pin "2") (pinfunction "2_2") (pintype "passive"))
      (node (ref "U17") (pin "3") (pinfunction "VCP_3") (pintype "bidirectional"))
    )
    (net (code "192") (name "Net-(U18-A2)") (class "Default")
      (node (ref "R22") (pin "1") (pinfunction "1_1") (pintype "passive"))
      (node (ref "U18") (pin "3") (pinfunction "A2_3") (pintype "input"))
    )
    (net (code "193") (name "Net-(X3B-1)") (class "Default")
      (node (ref "C59") (pin "1") (pinfunction "1_1") (pintype "passive"))
      (node (ref "D1") (pin "A") (pinfunction "A_A") (pintype "passive"))
      (node (ref "LED3") (pin "C") (pinfunction "C_C") (pintype "passive"))
      (node (ref "Q3") (pin "5") (pinfunction "D_5") (pintype "passive"))
      (node (ref "Q3") (pin "6") (pinfunction "D_6") (pintype "passive"))
      (node (ref "Q3") (pin "7") (pinfunction "D_7") (pintype "passive"))
      (node (ref "Q3") (pin "8") (pinfunction "D_8") (pintype "passive"))
      (node (ref "Q3") (pin "TH") (pinfunction "D_TH") (pintype "passive"))
      (node (ref "R55") (pin "1") (pinfunction "1_1") (pintype "passive"))
      (node (ref "X3") (pin "2") (pinfunction "1_2") (pintype "passive"))
    )
    (net (code "194") (name "Net-(X7B-S)") (class "Default")
      (node (ref "R17") (pin "1") (pinfunction "1_1") (pintype "passive"))
      (node (ref "R39") (pin "1") (pinfunction "1_1") (pintype "passive"))
      (node (ref "X7") (pin "2") (pinfunction "S_2") (pintype "passive"))
    )
    (net (code "195") (name "Net-(X8B-S)") (class "Default")
      (node (ref "R13") (pin "1") (pinfunction "1_1") (pintype "passive"))
      (node (ref "R38") (pin "1") (pinfunction "1_1") (pintype "passive"))
      (node (ref "X8") (pin "2") (pinfunction "S_2") (pintype "passive"))
    )
    (net (code "196") (name "Net-(X11B-S)") (class "Default")
      (node (ref "R18") (pin "1") (pinfunction "1_1") (pintype "passive"))
      (node (ref "R40") (pin "1") (pinfunction "1_1") (pintype "passive"))
      (node (ref "X11") (pin "2") (pinfunction "S_2") (pintype "passive"))
    )
    (net (code "197") (name "Net-(X20C-1)") (class "Default")
      (node (ref "C58") (pin "1") (pinfunction "1_1") (pintype "passive"))
      (node (ref "D2") (pin "A") (pinfunction "A_A") (pintype "passive"))
      (node (ref "LED2") (pin "C") (pinfunction "C_C") (pintype "passive"))
      (node (ref "Q1") (pin "5") (pinfunction "D_5") (pintype "passive"))
      (node (ref "Q1") (pin "6") (pinfunction "D_6") (pintype "passive"))
      (node (ref "Q1") (pin "7") (pinfunction "D_7") (pintype "passive"))
      (node (ref "Q1") (pin "8") (pinfunction "D_8") (pintype "passive"))
      (node (ref "Q1") (pin "TH") (pinfunction "D_TH") (pintype "passive"))
      (node (ref "R56") (pin "1") (pinfunction "1_1") (pintype "passive"))
      (node (ref "X20") (pin "3") (pinfunction "1_3") (pintype "passive"))
      (node (ref "X20") (pin "4") (pinfunction "1_4") (pintype "passive"))
    )
    (net (code "198") (name "Net-(X21B-1)") (class "Default")
      (node (ref "C57") (pin "1") (pinfunction "1_1") (pintype "passive"))
      (node (ref "D3") (pin "A") (pinfunction "A_A") (pintype "passive"))
      (node (ref "LED1") (pin "C") (pinfunction "C_C") (pintype "passive"))
      (node (ref "Q2") (pin "5") (pinfunction "D_5") (pintype "passive"))
      (node (ref "Q2") (pin "6") (pinfunction "D_6") (pintype "passive"))
      (node (ref "Q2") (pin "7") (pinfunction "D_7") (pintype "passive"))
      (node (ref "Q2") (pin "8") (pinfunction "D_8") (pintype "passive"))
      (node (ref "Q2") (pin "TH") (pinfunction "D_TH") (pintype "passive"))
      (node (ref "R57") (pin "1") (pinfunction "1_1") (pintype "passive"))
      (node (ref "X21") (pin "2") (pinfunction "1_2") (pintype "passive"))
    )
    (net (code "199") (name "unconnected-(P8-Pad3)") (class "Default")
      (node (ref "P8") (pin "3") (pinfunction "3_3") (pintype "passive"))
    )
    (net (code "200") (name "unconnected-(P8-Pad4)") (class "Default")
      (node (ref "P8") (pin "4") (pinfunction "4_4") (pintype "passive"))
    )
    (net (code "201") (name "unconnected-(P8-Pad5)") (class "Default")
      (node (ref "P8") (pin "5") (pinfunction "5_5") (pintype "passive"))
    )
    (net (code "202") (name "unconnected-(P8-Pad6)") (class "Default")
      (node (ref "P8") (pin "6") (pinfunction "6_6") (pintype "passive"))
    )
    (net (code "203") (name "unconnected-(P8-Pad7)") (class "Default")
      (node (ref "P8") (pin "7") (pinfunction "7_7") (pintype "passive"))
    )
    (net (code "204") (name "unconnected-(P8-Pad20)") (class "Default")
      (node (ref "P8") (pin "20") (pinfunction "20_20") (pintype "passive"))
    )
    (net (code "205") (name "unconnected-(P8-Pad21)") (class "Default")
      (node (ref "P8") (pin "21") (pinfunction "21_21") (pintype "passive"))
    )
    (net (code "206") (name "unconnected-(P8-Pad22)") (class "Default")
      (node (ref "P8") (pin "22") (pinfunction "22_22") (pintype "passive"))
    )
    (net (code "207") (name "unconnected-(P8-Pad23)") (class "Default")
      (node (ref "P8") (pin "23") (pinfunction "23_23") (pintype "passive"))
    )
    (net (code "208") (name "unconnected-(P8-Pad24)") (class "Default")
      (node (ref "P8") (pin "24") (pinfunction "24_24") (pintype "passive"))
    )
    (net (code "209") (name "unconnected-(P8-Pad25)") (class "Default")
      (node (ref "P8") (pin "25") (pinfunction "25_25") (pintype "passive"))
    )
    (net (code "210") (name "unconnected-(P8-Pad27)") (class "Default")
      (node (ref "P8") (pin "27") (pinfunction "27_27") (pintype "passive"))
    )
    (net (code "211") (name "unconnected-(P8-Pad28)") (class "Default")
      (node (ref "P8") (pin "28") (pinfunction "28_28") (pintype "passive"))
    )
    (net (code "212") (name "unconnected-(P8-Pad29)") (class "Default")
      (node (ref "P8") (pin "29") (pinfunction "29_29") (pintype "passive"))
    )
    (net (code "213") (name "unconnected-(P8-Pad30)") (class "Default")
      (node (ref "P8") (pin "30") (pinfunction "30_30") (pintype "passive"))
    )
    (net (code "214") (name "unconnected-(P8-Pad31)") (class "Default")
      (node (ref "P8") (pin "31") (pinfunction "31_31") (pintype "passive"))
    )
    (net (code "215") (name "unconnected-(P8-Pad32)") (class "Default")
      (node (ref "P8") (pin "32") (pinfunction "32_32") (pintype "passive"))
    )
    (net (code "216") (name "unconnected-(P8-Pad33)") (class "Default")
      (node (ref "P8") (pin "33") (pinfunction "33_33") (pintype "passive"))
    )
    (net (code "217") (name "unconnected-(P8-Pad34)") (class "Default")
      (node (ref "P8") (pin "34") (pinfunction "34_34") (pintype "passive"))
    )
    (net (code "218") (name "unconnected-(P8-Pad35)") (class "Default")
      (node (ref "P8") (pin "35") (pinfunction "35_35") (pintype "passive"))
    )
    (net (code "219") (name "unconnected-(P8-Pad36)") (class "Default")
      (node (ref "P8") (pin "36") (pinfunction "36_36") (pintype "passive"))
    )
    (net (code "220") (name "unconnected-(P8-Pad37)") (class "Default")
      (node (ref "P8") (pin "37") (pinfunction "37_37") (pintype "passive"))
    )
    (net (code "221") (name "unconnected-(P8-Pad38)") (class "Default")
      (node (ref "P8") (pin "38") (pinfunction "38_38") (pintype "passive"))
    )
    (net (code "222") (name "unconnected-(P8-Pad39)") (class "Default")
      (node (ref "P8") (pin "39") (pinfunction "39_39") (pintype "passive"))
    )
    (net (code "223") (name "unconnected-(P8-Pad40)") (class "Default")
      (node (ref "P8") (pin "40") (pinfunction "40_40") (pintype "passive"))
    )
    (net (code "224") (name "unconnected-(P8-Pad41)") (class "Default")
      (node (ref "P8") (pin "41") (pinfunction "41_41") (pintype "passive"))
    )
    (net (code "225") (name "unconnected-(P8-Pad42)") (class "Default")
      (node (ref "P8") (pin "42") (pinfunction "42_42") (pintype "passive"))
    )
    (net (code "226") (name "unconnected-(P8-Pad43)") (class "Default")
      (node (ref "P8") (pin "43") (pinfunction "43_43") (pintype "passive"))
    )
    (net (code "227") (name "unconnected-(P8-Pad44)") (class "Default")
      (node (ref "P8") (pin "44") (pinfunction "44_44") (pintype "passive"))
    )
    (net (code "228") (name "unconnected-(P8-Pad45)") (class "Default")
      (node (ref "P8") (pin "45") (pinfunction "45_45") (pintype "passive"))
    )
    (net (code "229") (name "unconnected-(P8-Pad46)") (class "Default")
      (node (ref "P8") (pin "46") (pinfunction "46_46") (pintype "passive"))
    )
    (net (code "230") (name "unconnected-(P9-Pad7)") (class "Default")
      (node (ref "P9") (pin "7") (pinfunction "7_7") (pintype "passive"))
    )
    (net (code "231") (name "unconnected-(P9-Pad9)") (class "Default")
      (node (ref "P9") (pin "9") (pinfunction "9_9") (pintype "passive"))
    )
    (net (code "232") (name "unconnected-(P9-Pad10)") (class "Default")
      (node (ref "P9") (pin "10") (pinfunction "10_10") (pintype "passive"))
    )
    (net (code "233") (name "unconnected-(P9-Pad15)") (class "Default")
      (node (ref "P9") (pin "15") (pinfunction "15_15") (pintype "passive"))
    )
    (net (code "234") (name "unconnected-(P9-Pad17)") (class "Default")
      (node (ref "P9") (pin "17") (pinfunction "17_17") (pintype "passive"))
    )
    (net (code "235") (name "unconnected-(P9-Pad21)") (class "Default")
      (node (ref "P9") (pin "21") (pinfunction "21_21") (pintype "passive"))
    )
    (net (code "236") (name "unconnected-(P9-Pad26)") (class "Default")
      (node (ref "P9") (pin "26") (pinfunction "26_26") (pintype "passive"))
    )
    (net (code "237") (name "unconnected-(P9-Pad27)") (class "Default")
      (node (ref "P9") (pin "27") (pinfunction "27_27") (pintype "passive"))
    )
    (net (code "238") (name "unconnected-(P9-Pad34)") (class "Default")
      (node (ref "P9") (pin "34") (pinfunction "34_34") (pintype "passive"))
    )
    (net (code "239") (name "unconnected-(P9-Pad37)") (class "Default")
      (node (ref "P9") (pin "37") (pinfunction "37_37") (pintype "passive"))
    )
    (net (code "240") (name "unconnected-(P9-Pad38)") (class "Default")
      (node (ref "P9") (pin "38") (pinfunction "38_38") (pintype "passive"))
    )
    (net (code "241") (name "unconnected-(P9-Pad39)") (class "Default")
      (node (ref "P9") (pin "39") (pinfunction "39_39") (pintype "passive"))
    )
    (net (code "242") (name "unconnected-(P9-Pad40)") (class "Default")
      (node (ref "P9") (pin "40") (pinfunction "40_40") (pintype "passive"))
    )
    (net (code "243") (name "unconnected-(U3-QA-Pad15)") (class "Default")
      (node (ref "U3") (pin "15") (pinfunction "QA_15") (pintype "output"))
    )
    (net (code "244") (name "unconnected-(U4-QA-Pad15)") (class "Default")
      (node (ref "U4") (pin "15") (pinfunction "QA_15") (pintype "output"))
    )
    (net (code "245") (name "unconnected-(U5-QA-Pad15)") (class "Default")
      (node (ref "U5") (pin "15") (pinfunction "QA_15") (pintype "output"))
    )
    (net (code "246") (name "unconnected-(U5-QH_2-Pad9)") (class "Default")
      (node (ref "U5") (pin "9") (pinfunction "QH_2_9") (pintype "output"))
    )
    (net (code "247") (name "unconnected-(U6-EN-Pad9)") (class "Default")
      (node (ref "U6") (pin "9") (pinfunction "EN_9") (pintype "input"))
    )
    (net (code "248") (name "unconnected-(U10-EN-Pad9)") (class "Default")
      (node (ref "U10") (pin "9") (pinfunction "EN_9") (pintype "input"))
    )
    (net (code "249") (name "unconnected-(U11-EXTCLK-Pad25)") (class "Default")
      (node (ref "U11") (pin "25") (pinfunction "EXTCLK_25") (pintype "input"))
    )
    (net (code "250") (name "unconnected-(U11-LED0-Pad6)") (class "Default")
      (node (ref "U11") (pin "6") (pinfunction "LED0_6") (pintype "output"))
    )
    (net (code "251") (name "unconnected-(U11-LED1-Pad7)") (class "Default")
      (node (ref "U11") (pin "7") (pinfunction "LED1_7") (pintype "output"))
    )
    (net (code "252") (name "unconnected-(U11-LED2-Pad8)") (class "Default")
      (node (ref "U11") (pin "8") (pinfunction "LED2_8") (pintype "output"))
    )
    (net (code "253") (name "unconnected-(U11-LED6-Pad12)") (class "Default")
      (node (ref "U11") (pin "12") (pinfunction "LED6_12") (pintype "output"))
    )
    (net (code "254") (name "unconnected-(U13-HOME-Pad27)") (class "Default")
      (node (ref "U13") (pin "27") (pinfunction "HOME_27") (pintype "output"))
    )
    (net (code "255") (name "unconnected-(U13-V3P3OUT-Pad15)") (class "Default")
      (node (ref "U13") (pin "15") (pinfunction "V3P3OUT_15") (pintype "output"))
    )
    (net (code "256") (name "unconnected-(U14-HOME-Pad27)") (class "Default")
      (node (ref "U14") (pin "27") (pinfunction "HOME_27") (pintype "output"))
    )
    (net (code "257") (name "unconnected-(U14-V3P3OUT-Pad15)") (class "Default")
      (node (ref "U14") (pin "15") (pinfunction "V3P3OUT_15") (pintype "output"))
    )
    (net (code "258") (name "unconnected-(U15-HOME-Pad27)") (class "Default")
      (node (ref "U15") (pin "27") (pinfunction "HOME_27") (pintype "output"))
    )
    (net (code "259") (name "unconnected-(U15-V3P3OUT-Pad15)") (class "Default")
      (node (ref "U15") (pin "15") (pinfunction "V3P3OUT_15") (pintype "output"))
    )
    (net (code "260") (name "unconnected-(U16-HOME-Pad27)") (class "Default")
      (node (ref "U16") (pin "27") (pinfunction "HOME_27") (pintype "output"))
    )
    (net (code "261") (name "unconnected-(U16-V3P3OUT-Pad15)") (class "Default")
      (node (ref "U16") (pin "15") (pinfunction "V3P3OUT_15") (pintype "output"))
    )
    (net (code "262") (name "unconnected-(U17-HOME-Pad27)") (class "Default")
      (node (ref "U17") (pin "27") (pinfunction "HOME_27") (pintype "output"))
    )
    (net (code "263") (name "unconnected-(U17-V3P3OUT-Pad15)") (class "Default")
      (node (ref "U17") (pin "15") (pinfunction "V3P3OUT_15") (pintype "output"))
    )
    (net (code "264") (name "unconnected-(U18-~{WC}-Pad7)") (class "Default")
      (node (ref "U18") (pin "7") (pinfunction "~{WC}_7") (pintype "no_connect"))
    )
    (net (code "265") (name "unconnected-(U19-NC-Pad16)") (class "Default")
      (node (ref "U19") (pin "16") (pinfunction "NC_16") (pintype "no_connect"))
    )
    (net (code "266") (name "unconnected-(U19-NC_2-Pad13)") (class "Default")
      (node (ref "U19") (pin "13") (pinfunction "NC_2_13") (pintype "no_connect"))
    )
    (net (code "267") (name "unconnected-(X23A-S-Pad1)") (class "Default")
      (node (ref "X23") (pin "1") (pinfunction "S_1") (pintype "passive"))
    )
    (net (code "268") (name "unconnected-(X23B-S-Pad2)") (class "Default")
      (node (ref "X23") (pin "2") (pinfunction "S_2") (pintype "passive"))
    )
    (net (code "269") (name "unconnected-(X23C-S-Pad3)") (class "Default")
      (node (ref "X23") (pin "3") (pinfunction "S_3") (pintype "passive"))
    )
  )
)
